# FMC_prototype.net
KiCad netlist of a schematic drawn in EAGLE
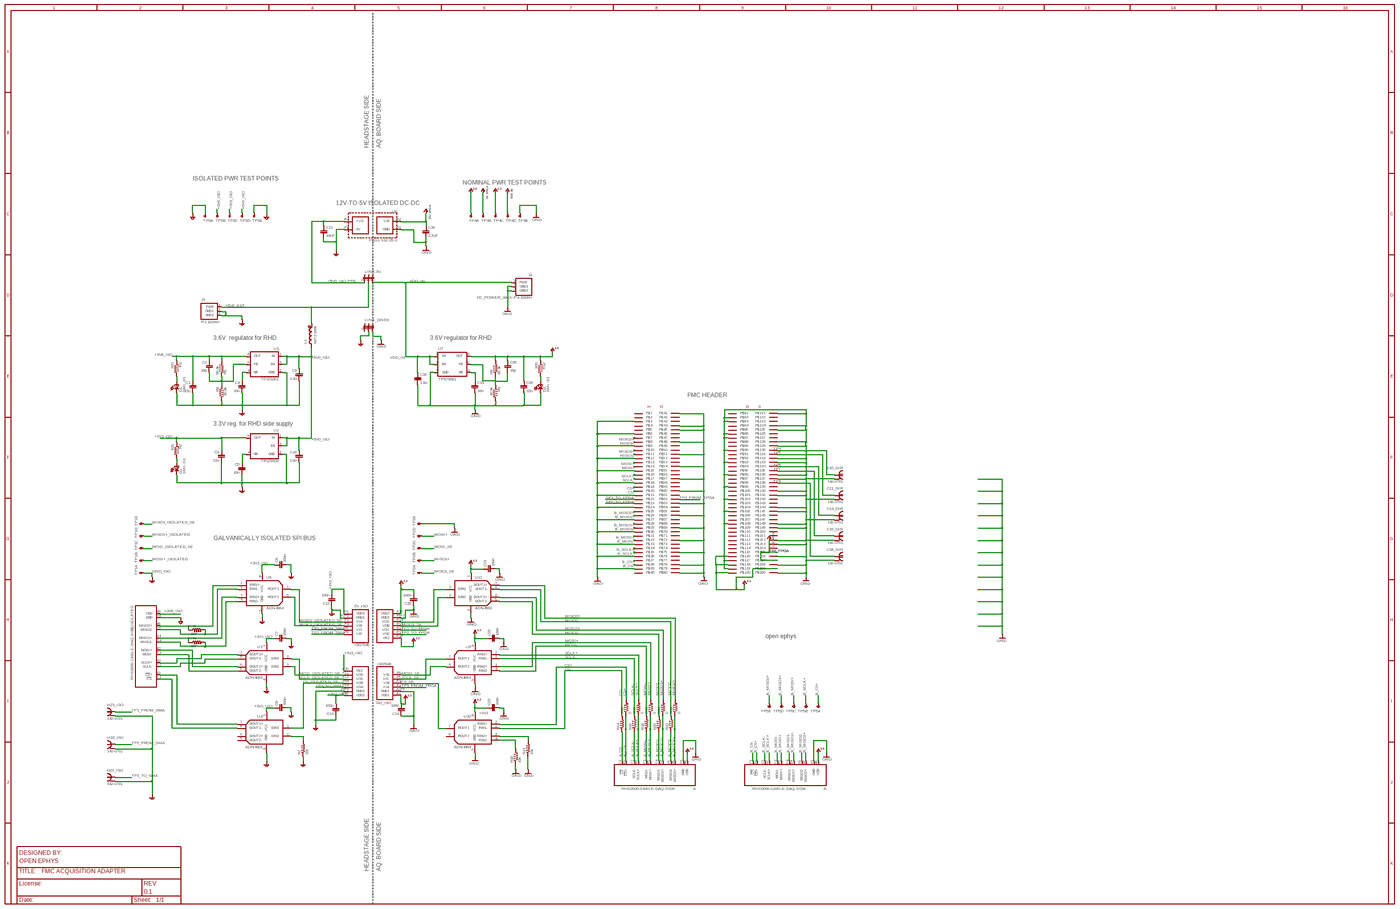
[diagram p0: schematic, sheet 1, overview]
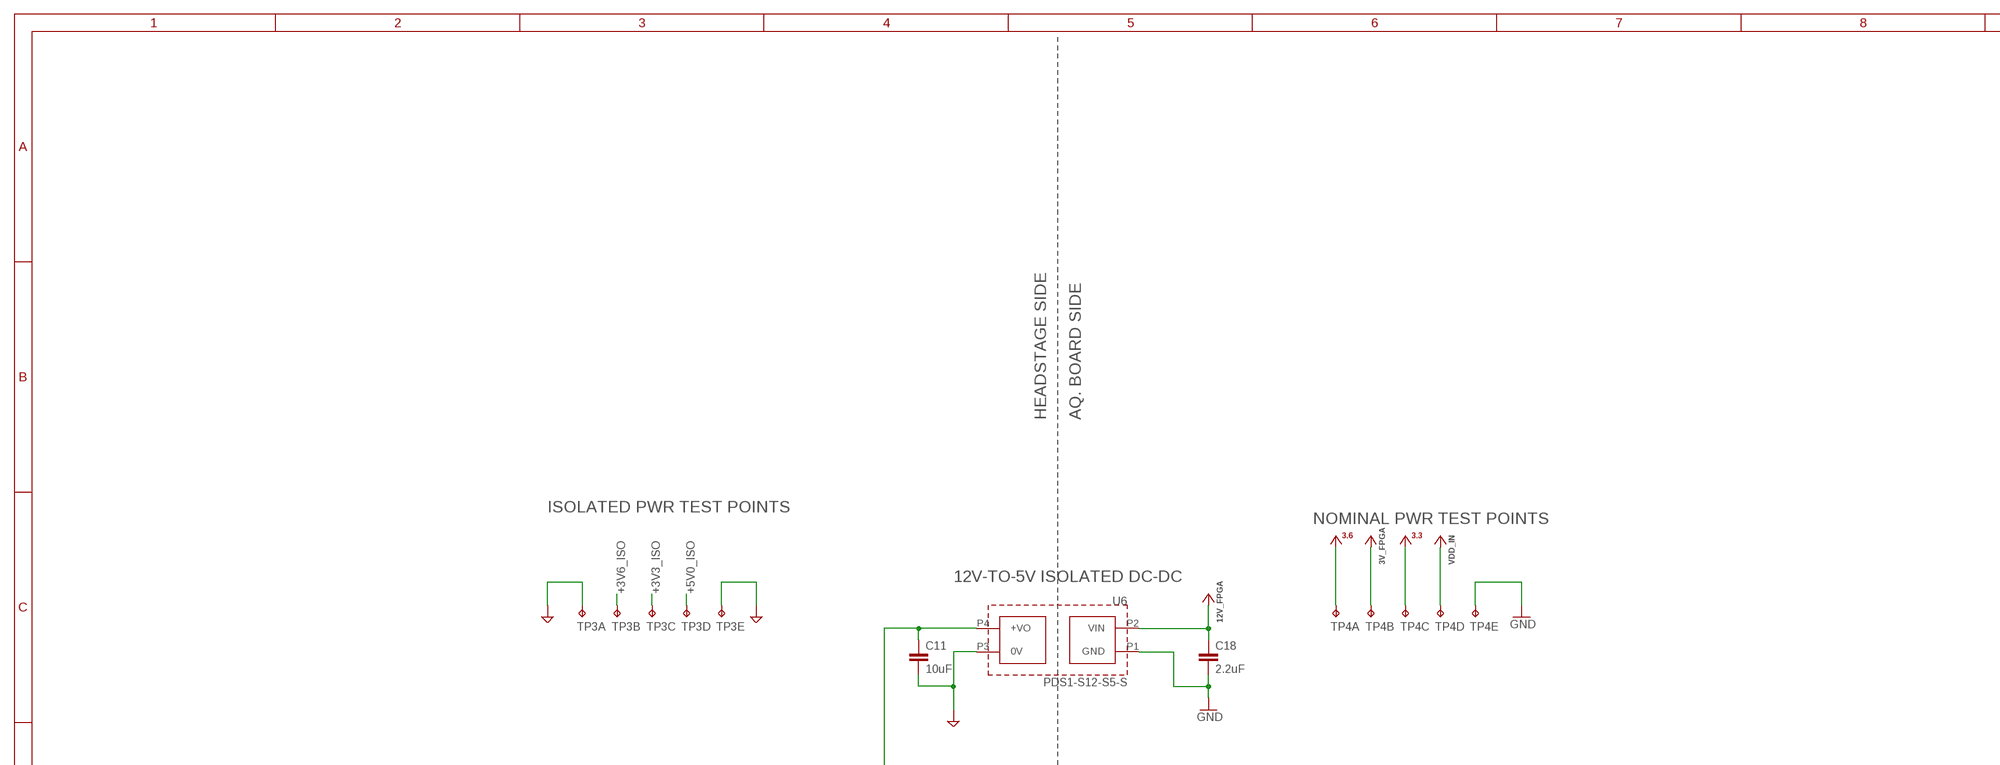
[diagram p1: schematic, sheet 1, part 1 of 4]
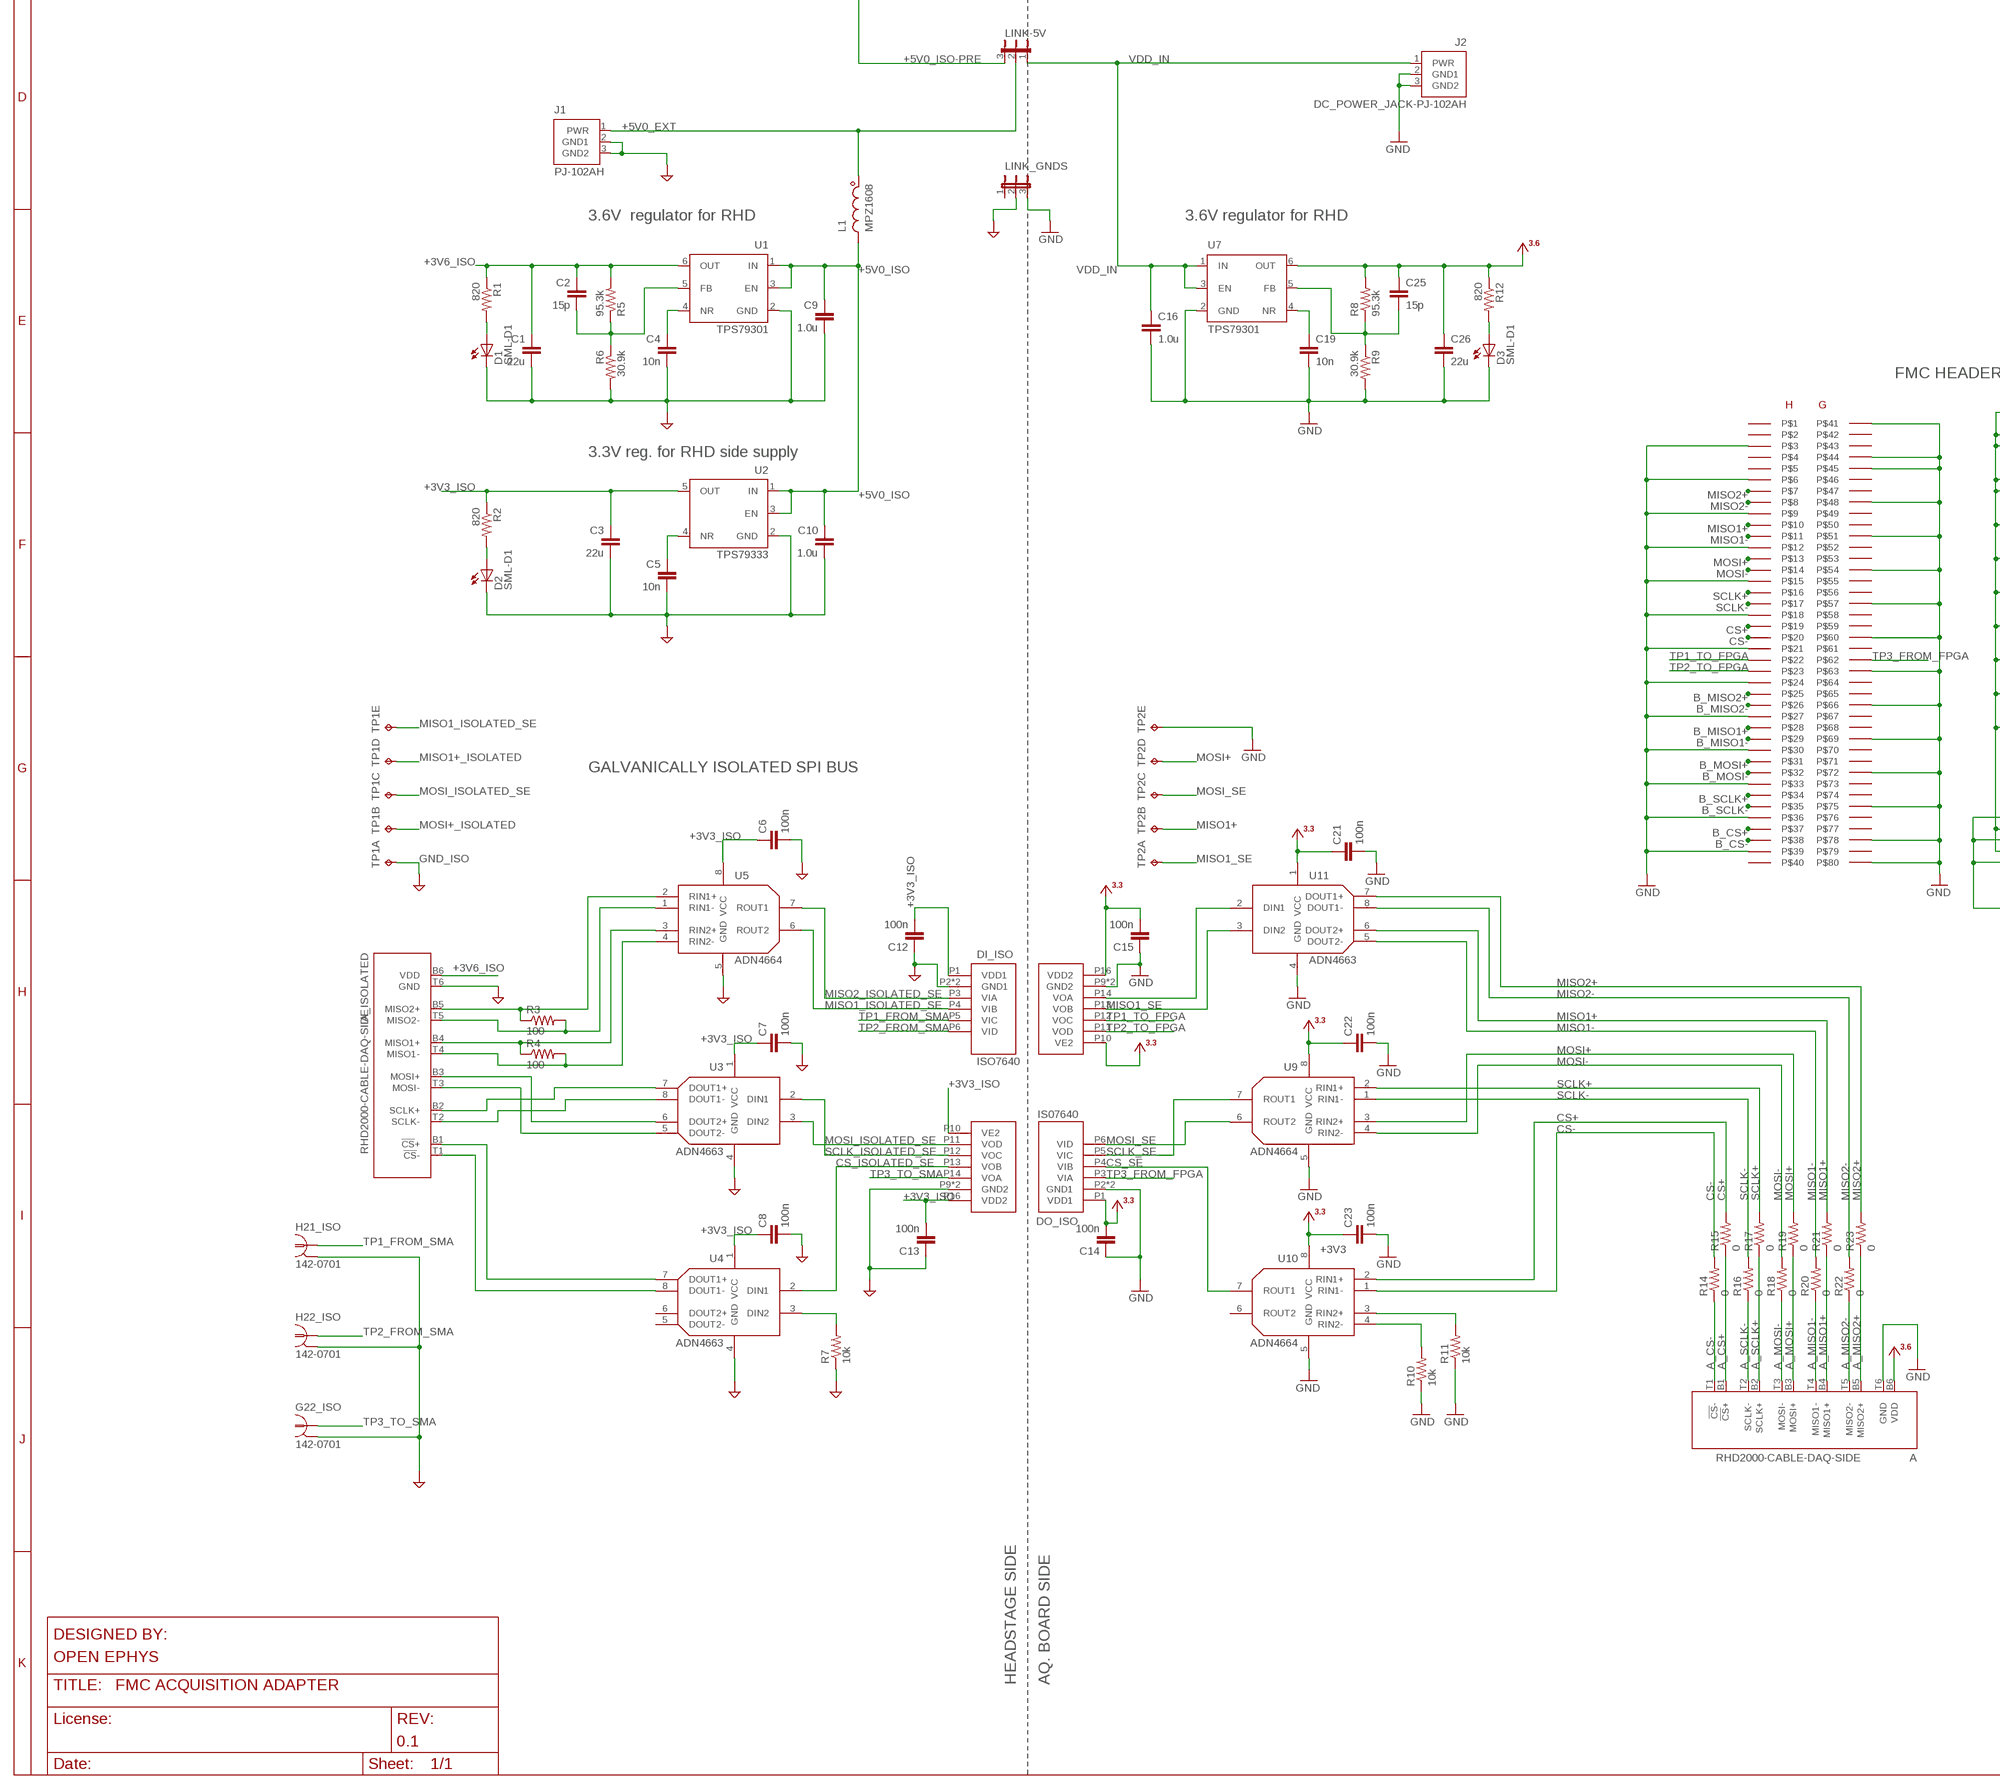
[diagram p2: schematic, sheet 1, part 2 of 4]
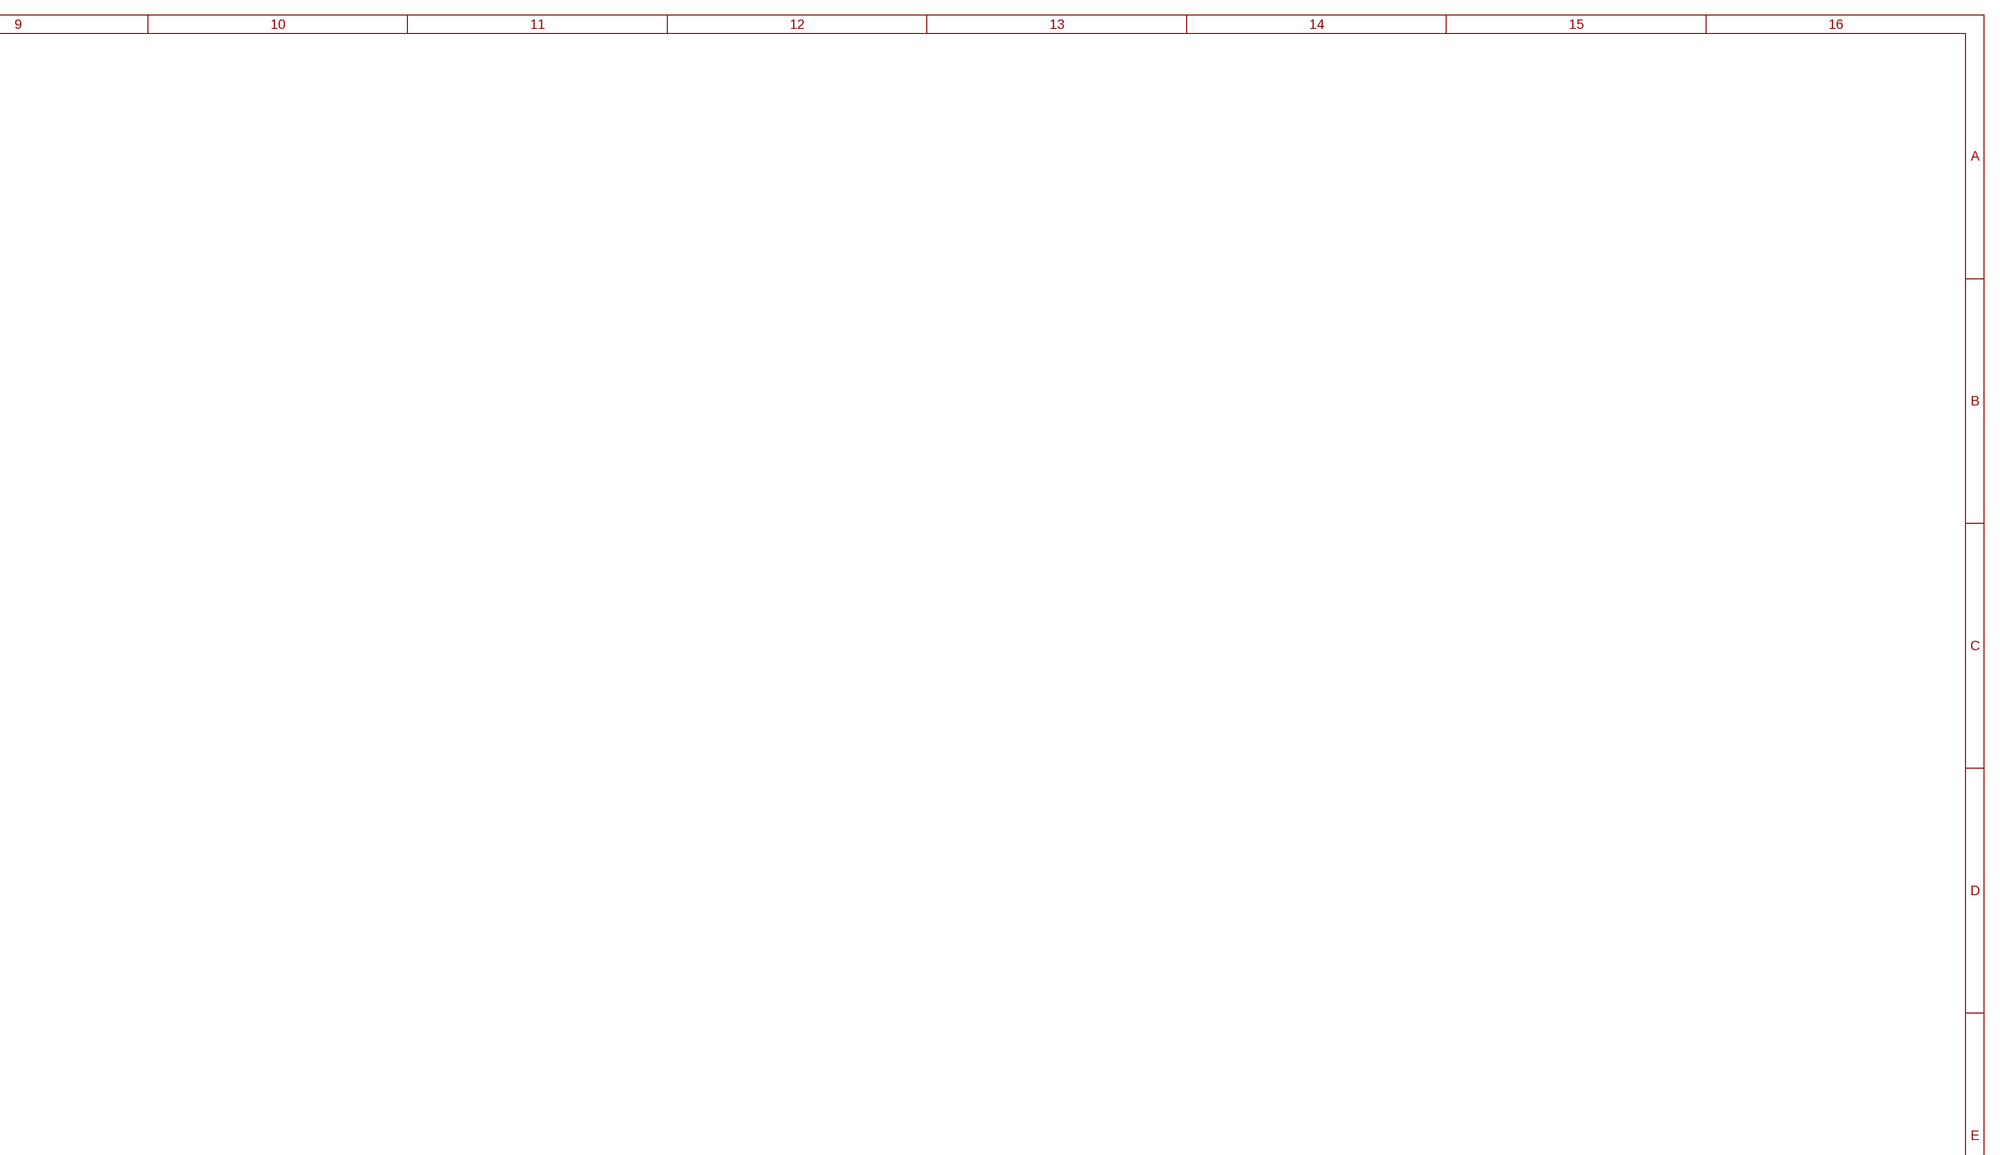
[diagram p3: schematic, sheet 1, part 3 of 4]
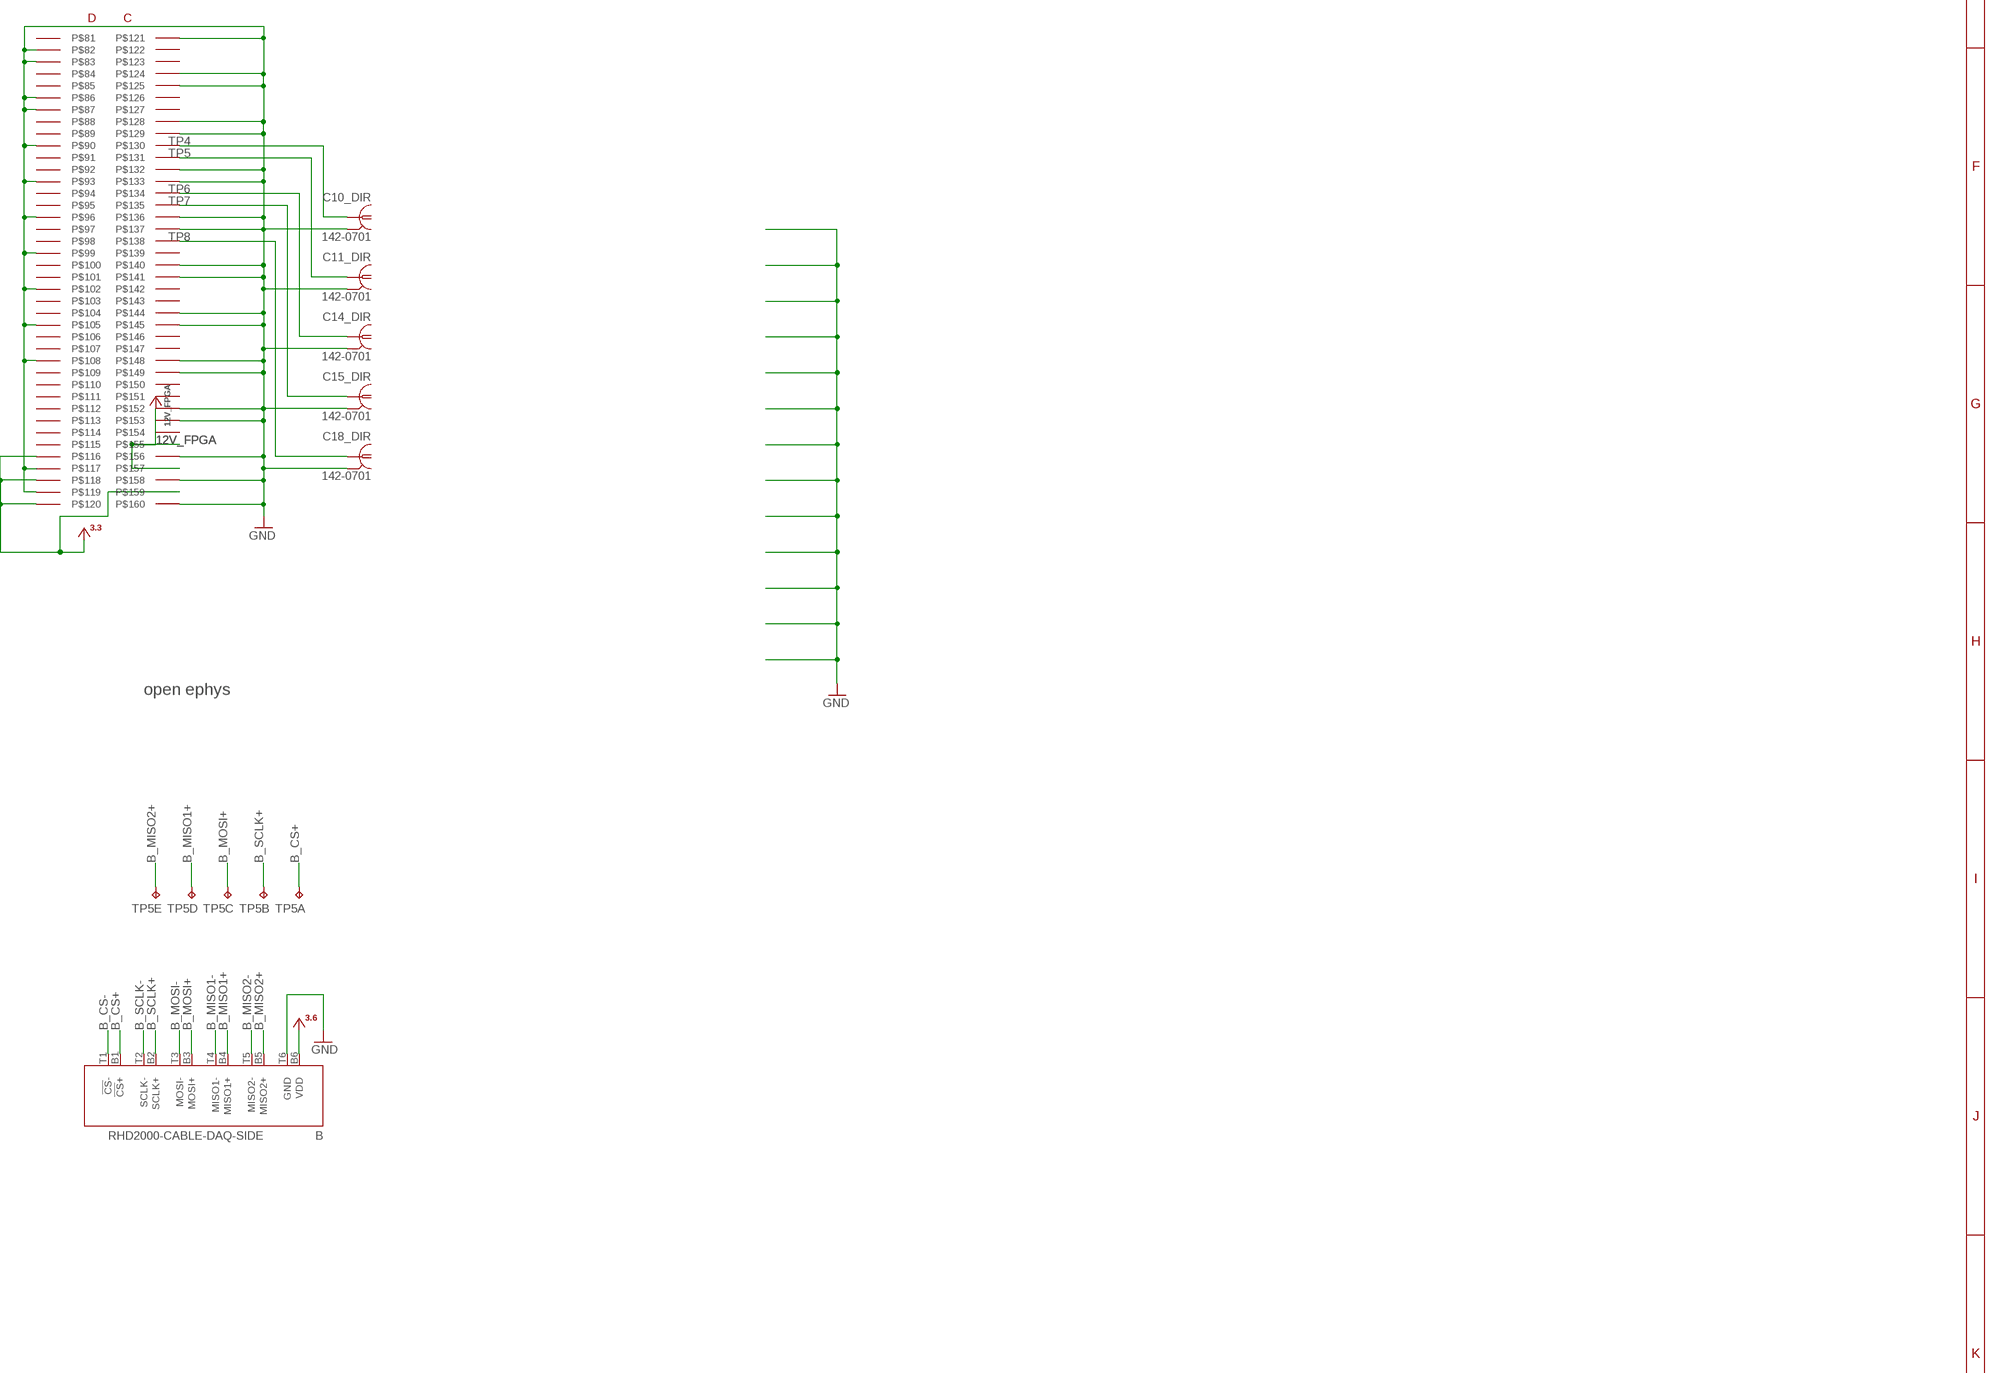
[diagram p4: schematic, sheet 1, part 4 of 4]

(export (version "E")
  (design (tool "Eeschema 10.0.6"))
  (components
    (comp (ref "A")
      (value "RHD2000-CABLE-DAQ-SIDE")
      (footprint "eagle-import:OMNETICS_PZN-12-AA")
      (libsource (lib "eagle-import") (part "RHD2000-CABLE-DAQ-SIDE"))
    )
    (comp (ref "A_ISOLATED")
      (value "RHD2000-CABLE-DAQ-SIDE")
      (footprint "eagle-import:OMNETICS_PZN-12-AA")
      (libsource (lib "eagle-import") (part "RHD2000-CABLE-DAQ-SIDE"))
    )
    (comp (ref "B")
      (value "RHD2000-CABLE-DAQ-SIDE")
      (footprint "eagle-import:OMNETICS_PZN-12-AA")
      (libsource (lib "eagle-import") (part "RHD2000-CABLE-DAQ-SIDE"))
    )
    (comp (ref "C1")
      (value "22u")
      (footprint "eagle-import:1206")
      (libsource (lib "eagle-import") (part "C_1206"))
    )
    (comp (ref "C2")
      (value "15p")
      (footprint "eagle-import:0603")
      (libsource (lib "eagle-import") (part "C_0603"))
    )
    (comp (ref "C3")
      (value "22u")
      (footprint "eagle-import:1206")
      (libsource (lib "eagle-import") (part "C_1206"))
    )
    (comp (ref "C4")
      (value "10n")
      (footprint "eagle-import:0603")
      (libsource (lib "eagle-import") (part "C_0603"))
    )
    (comp (ref "C5")
      (value "10n")
      (footprint "eagle-import:0603")
      (libsource (lib "eagle-import") (part "C_0603"))
    )
    (comp (ref "C6")
      (value "100n")
      (footprint "eagle-import:0603")
      (libsource (lib "eagle-import") (part "C_0603"))
    )
    (comp (ref "C7")
      (value "100n")
      (footprint "eagle-import:0603")
      (libsource (lib "eagle-import") (part "C_0603"))
    )
    (comp (ref "C8")
      (value "100n")
      (footprint "eagle-import:0603")
      (libsource (lib "eagle-import") (part "C_0603"))
    )
    (comp (ref "C9")
      (value "1.0u")
      (footprint "eagle-import:0805")
      (libsource (lib "eagle-import") (part "C_0805"))
    )
    (comp (ref "C10")
      (value "1.0u")
      (footprint "eagle-import:0805")
      (libsource (lib "eagle-import") (part "C_0805"))
    )
    (comp (ref "C10_DIR")
      (value "142-0701")
      (footprint "eagle-import:SMA_JACK_142-0701-201")
      (libsource (lib "eagle-import") (part "COAX_SMA-VERT"))
    )
    (comp (ref "C11")
      (value "10uF")
      (footprint "eagle-import:1206")
      (libsource (lib "eagle-import") (part "jonnew_C_1206"))
    )
    (comp (ref "C11_DIR")
      (value "142-0701")
      (footprint "eagle-import:SMA_JACK_142-0701-201")
      (libsource (lib "eagle-import") (part "COAX_SMA-VERT"))
    )
    (comp (ref "C12")
      (value "100n")
      (footprint "eagle-import:0603")
      (libsource (lib "eagle-import") (part "C_0603"))
    )
    (comp (ref "C13")
      (value "100n")
      (footprint "eagle-import:0603")
      (libsource (lib "eagle-import") (part "C_0603"))
    )
    (comp (ref "C14")
      (value "100n")
      (footprint "eagle-import:0603")
      (libsource (lib "eagle-import") (part "C_0603"))
    )
    (comp (ref "C14_DIR")
      (value "142-0701")
      (footprint "eagle-import:SMA_JACK_142-0701-201")
      (libsource (lib "eagle-import") (part "COAX_SMA-VERT"))
    )
    (comp (ref "C15")
      (value "100n")
      (footprint "eagle-import:0603")
      (libsource (lib "eagle-import") (part "C_0603"))
    )
    (comp (ref "C15_DIR")
      (value "142-0701")
      (footprint "eagle-import:SMA_JACK_142-0701-201")
      (libsource (lib "eagle-import") (part "COAX_SMA-VERT"))
    )
    (comp (ref "C16")
      (value "1.0u")
      (footprint "eagle-import:0805")
      (libsource (lib "eagle-import") (part "C_0805"))
    )
    (comp (ref "C18")
      (value "2.2uF")
      (footprint "eagle-import:1206")
      (libsource (lib "eagle-import") (part "jonnew_C_1206"))
    )
    (comp (ref "C18_DIR")
      (value "142-0701")
      (footprint "eagle-import:SMA_JACK_142-0701-201")
      (libsource (lib "eagle-import") (part "COAX_SMA-VERT"))
    )
    (comp (ref "C19")
      (value "10n")
      (footprint "eagle-import:0603")
      (libsource (lib "eagle-import") (part "C_0603"))
    )
    (comp (ref "C21")
      (value "100n")
      (footprint "eagle-import:0603")
      (libsource (lib "eagle-import") (part "C_0603"))
    )
    (comp (ref "C22")
      (value "100n")
      (footprint "eagle-import:0603")
      (libsource (lib "eagle-import") (part "C_0603"))
    )
    (comp (ref "C23")
      (value "100n")
      (footprint "eagle-import:0603")
      (libsource (lib "eagle-import") (part "C_0603"))
    )
    (comp (ref "C25")
      (value "15p")
      (footprint "eagle-import:0603")
      (libsource (lib "eagle-import") (part "C_0603"))
    )
    (comp (ref "C26")
      (value "22u")
      (footprint "eagle-import:1206")
      (libsource (lib "eagle-import") (part "C_1206"))
    )
    (comp (ref "D1")
      (value "SML-D1")
      (footprint "eagle-import:LED-0603")
      (libsource (lib "eagle-import") (part "LED_0603"))
    )
    (comp (ref "D2")
      (value "SML-D1")
      (footprint "eagle-import:LED-0603")
      (libsource (lib "eagle-import") (part "LED_0603"))
    )
    (comp (ref "D3")
      (value "SML-D1")
      (footprint "eagle-import:LED-0603")
      (libsource (lib "eagle-import") (part "LED_0603"))
    )
    (comp (ref "DI_ISO")
      (value "ISO7640")
      (footprint "eagle-import:SOIC_WIDE_16")
      (libsource (lib "eagle-import") (part "ADUM3440"))
    )
    (comp (ref "DO_ISO")
      (value "IS07640")
      (footprint "eagle-import:SOIC_WIDE_16")
      (libsource (lib "eagle-import") (part "ADUM3440"))
    )
    (comp (ref "FMC")
      (value "FMC_LPC_160_PIN")
      (footprint "eagle-import:FMC_LPC_MALE_WITH_SP601_BSILK")
      (libsource (lib "eagle-import") (part "FMC_LPC_160_PIN"))
    )
    (comp (ref "G22_ISO")
      (value "142-0701")
      (footprint "eagle-import:SMA_JACK_142-0701-201")
      (libsource (lib "eagle-import") (part "COAX_SMA-VERT"))
    )
    (comp (ref "H21_ISO")
      (value "142-0701")
      (footprint "eagle-import:SMA_JACK_142-0701-201")
      (libsource (lib "eagle-import") (part "COAX_SMA-VERT"))
    )
    (comp (ref "H22_ISO")
      (value "142-0701")
      (footprint "eagle-import:SMA_JACK_142-0701-201")
      (libsource (lib "eagle-import") (part "COAX_SMA-VERT"))
    )
    (comp (ref "J1")
      (value "PJ-102AH")
      (footprint "eagle-import:PJ-102AH")
      (libsource (lib "eagle-import") (part "DC_POWER_JACK-PJ-102AH"))
    )
    (comp (ref "J2")
      (value "DC_POWER_JACK-PJ-102AH")
      (footprint "eagle-import:PJ-102AH")
      (libsource (lib "eagle-import") (part "DC_POWER_JACK-PJ-102AH"))
    )
    (comp (ref "L1")
      (value "MPZ1608")
      (footprint "eagle-import:0603")
      (libsource (lib "eagle-import") (part "L_0603"))
    )
    (comp (ref "LINK-5V")
      (value "JP2E")
      (footprint "eagle-import:JP2")
      (libsource (lib "eagle-import") (part "JP2E"))
    )
    (comp (ref "LINK_GNDS")
      (value "JP2E")
      (footprint "eagle-import:JP2")
      (libsource (lib "eagle-import") (part "JP2E"))
    )
    (comp (ref "R1")
      (value "820")
      (footprint "eagle-import:0603")
      (libsource (lib "eagle-import") (part "R_0603"))
    )
    (comp (ref "R2")
      (value "820")
      (footprint "eagle-import:0603")
      (libsource (lib "eagle-import") (part "R_0603"))
    )
    (comp (ref "R3")
      (value "100")
      (footprint "eagle-import:0603")
      (libsource (lib "eagle-import") (part "R_0603"))
    )
    (comp (ref "R4")
      (value "100")
      (footprint "eagle-import:0603")
      (libsource (lib "eagle-import") (part "R_0603"))
    )
    (comp (ref "R5")
      (value "95.3k")
      (footprint "eagle-import:0603")
      (libsource (lib "eagle-import") (part "R_0603"))
    )
    (comp (ref "R6")
      (value "30.9k")
      (footprint "eagle-import:0603")
      (libsource (lib "eagle-import") (part "R_0603"))
    )
    (comp (ref "R7")
      (value "10k")
      (footprint "eagle-import:0603")
      (libsource (lib "eagle-import") (part "R_0603"))
    )
    (comp (ref "R8")
      (value "95.3k")
      (footprint "eagle-import:0603")
      (libsource (lib "eagle-import") (part "R_0603"))
    )
    (comp (ref "R9")
      (value "30.9k")
      (footprint "eagle-import:0603")
      (libsource (lib "eagle-import") (part "R_0603"))
    )
    (comp (ref "R10")
      (value "10k")
      (footprint "eagle-import:0603")
      (libsource (lib "eagle-import") (part "R_0603"))
    )
    (comp (ref "R11")
      (value "10k")
      (footprint "eagle-import:0603")
      (libsource (lib "eagle-import") (part "R_0603"))
    )
    (comp (ref "R12")
      (value "820")
      (footprint "eagle-import:0603")
      (libsource (lib "eagle-import") (part "R_0603"))
    )
    (comp (ref "R14")
      (value "0")
      (footprint "eagle-import:0603")
      (libsource (lib "eagle-import") (part "R_0603"))
    )
    (comp (ref "R15")
      (value "0")
      (footprint "eagle-import:0603")
      (libsource (lib "eagle-import") (part "R_0603"))
    )
    (comp (ref "R16")
      (value "0")
      (footprint "eagle-import:0603")
      (libsource (lib "eagle-import") (part "R_0603"))
    )
    (comp (ref "R17")
      (value "0")
      (footprint "eagle-import:0603")
      (libsource (lib "eagle-import") (part "R_0603"))
    )
    (comp (ref "R18")
      (value "0")
      (footprint "eagle-import:0603")
      (libsource (lib "eagle-import") (part "R_0603"))
    )
    (comp (ref "R19")
      (value "0")
      (footprint "eagle-import:0603")
      (libsource (lib "eagle-import") (part "R_0603"))
    )
    (comp (ref "R20")
      (value "0")
      (footprint "eagle-import:0603")
      (libsource (lib "eagle-import") (part "R_0603"))
    )
    (comp (ref "R21")
      (value "0")
      (footprint "eagle-import:0603")
      (libsource (lib "eagle-import") (part "R_0603"))
    )
    (comp (ref "R22")
      (value "0")
      (footprint "eagle-import:0603")
      (libsource (lib "eagle-import") (part "R_0603"))
    )
    (comp (ref "R23")
      (value "0")
      (footprint "eagle-import:0603")
      (libsource (lib "eagle-import") (part "R_0603"))
    )
    (comp (ref "TP1")
      (value "TP5P5-25-13")
      (footprint "eagle-import:P5-25-13")
      (libsource (lib "eagle-import") (part "TP5P5-25-13"))
    )
    (comp (ref "TP2")
      (value "TP5P5-25-13")
      (footprint "eagle-import:P5-25-13")
      (libsource (lib "eagle-import") (part "TP5P5-25-13"))
    )
    (comp (ref "TP3")
      (value "TP5P5-25-13")
      (footprint "eagle-import:P5-25-13")
      (libsource (lib "eagle-import") (part "TP5P5-25-13"))
    )
    (comp (ref "TP4")
      (value "TP5P5-25-13")
      (footprint "eagle-import:P5-25-13")
      (libsource (lib "eagle-import") (part "TP5P5-25-13"))
    )
    (comp (ref "TP5")
      (value "TP5P5-25-13")
      (footprint "eagle-import:P5-25-13")
      (libsource (lib "eagle-import") (part "TP5P5-25-13"))
    )
    (comp (ref "U$1")
      (value "OPEN_EPHYS_LOGO")
      (footprint "eagle-import:OPEN_EPHYS_LOGO")
      (libsource (lib "eagle-import") (part "OPEN_EPHYS_LOGO"))
    )
    (comp (ref "U1")
      (value "TPS79301")
      (footprint "eagle-import:SOT-23-6")
      (libsource (lib "eagle-import") (part "TPS79301"))
    )
    (comp (ref "U2")
      (value "TPS79333")
      (footprint "eagle-import:SOT-23-5")
      (libsource (lib "eagle-import") (part "TPS79333"))
    )
    (comp (ref "U3")
      (value "ADN4663")
      (footprint "eagle-import:SOIC127P500X400-8N")
      (libsource (lib "eagle-import") (part "ADN4663_SOIC"))
    )
    (comp (ref "U4")
      (value "ADN4663")
      (footprint "eagle-import:SOIC127P500X400-8N")
      (libsource (lib "eagle-import") (part "ADN4663_SOIC"))
    )
    (comp (ref "U5")
      (value "ADN4664")
      (footprint "eagle-import:SOIC127P500X400-8N")
      (libsource (lib "eagle-import") (part "ADN4664_SOIC"))
    )
    (comp (ref "U6")
      (value "PDS1-S12-S5-S")
      (footprint "eagle-import:PDS1")
      (libsource (lib "eagle-import") (part "PDS1"))
    )
    (comp (ref "U7")
      (value "TPS79301")
      (footprint "eagle-import:SOT-23-6")
      (libsource (lib "eagle-import") (part "TPS79301"))
    )
    (comp (ref "U9")
      (value "ADN4664")
      (footprint "eagle-import:SOIC127P500X400-8N")
      (libsource (lib "eagle-import") (part "ADN4664_SOIC"))
    )
    (comp (ref "U10")
      (value "ADN4664")
      (footprint "eagle-import:SOIC127P500X400-8N")
      (libsource (lib "eagle-import") (part "ADN4664_SOIC"))
    )
    (comp (ref "U11")
      (value "ADN4663")
      (footprint "eagle-import:SOIC127P500X400-8N")
      (libsource (lib "eagle-import") (part "ADN4663_SOIC"))
    )
  )
  (nets
    (net (code "1") (name "+3V3") (class "Default")
      (node (ref "C14") (pin "2") (pinfunction "2_2") (pintype "passive"))
      (node (ref "C15") (pin "2") (pinfunction "2_2") (pintype "passive"))
      (node (ref "C21") (pin "1") (pinfunction "1_1") (pintype "passive"))
      (node (ref "C22") (pin "1") (pinfunction "1_1") (pintype "passive"))
      (node (ref "C23") (pin "1") (pinfunction "1_1") (pintype "passive"))
      (node (ref "DI_ISO") (pin "P10") (pinfunction "VE2_P10") (pintype "bidirectional"))
      (node (ref "DI_ISO") (pin "P16") (pinfunction "VDD2_P16") (pintype "bidirectional"))
      (node (ref "DO_ISO") (pin "P1") (pinfunction "VDD1_P1") (pintype "bidirectional"))
      (node (ref "FMC") (pin "P$116") (pinfunction "P$116_P$116") (pintype "bidirectional"))
      (node (ref "FMC") (pin "P$118") (pinfunction "P$118_P$118") (pintype "bidirectional"))
      (node (ref "FMC") (pin "P$120") (pinfunction "P$120_P$120") (pintype "bidirectional"))
      (node (ref "FMC") (pin "P$159") (pinfunction "P$159_P$159") (pintype "bidirectional"))
      (node (ref "TP4") (pin "TP-2") (pinfunction "TP_TP-2") (pintype "input"))
      (node (ref "TP4") (pin "TP-3") (pinfunction "TP_TP-3") (pintype "input"))
      (node (ref "U10") (pin "8") (pinfunction "VCC_8") (pintype "bidirectional"))
      (node (ref "U11") (pin "1") (pinfunction "VCC_1") (pintype "bidirectional"))
      (node (ref "U9") (pin "8") (pinfunction "VCC_8") (pintype "bidirectional"))
    )
    (net (code "2") (name "+3V6") (class "Default")
      (node (ref "A") (pin "B6") (pinfunction "VDD_B6") (pintype "bidirectional"))
      (node (ref "B") (pin "B6") (pinfunction "VDD_B6") (pintype "bidirectional"))
      (node (ref "C25") (pin "1") (pinfunction "1_1") (pintype "passive"))
      (node (ref "C26") (pin "1") (pinfunction "1_1") (pintype "passive"))
      (node (ref "R12") (pin "1") (pinfunction "1_1") (pintype "passive"))
      (node (ref "R8") (pin "2") (pinfunction "2_2") (pintype "passive"))
      (node (ref "TP4") (pin "TP-1") (pinfunction "TP_TP-1") (pintype "input"))
      (node (ref "U7") (pin "6") (pinfunction "OUT_6") (pintype "power_in"))
    )
    (net (code "3") (name "/+3V3_ISO") (class "Default")
      (node (ref "C12") (pin "2") (pinfunction "2_2") (pintype "passive"))
      (node (ref "C13") (pin "2") (pinfunction "2_2") (pintype "passive"))
      (node (ref "C3") (pin "1") (pinfunction "1_1") (pintype "passive"))
      (node (ref "C6") (pin "1") (pinfunction "1_1") (pintype "passive"))
      (node (ref "C7") (pin "1") (pinfunction "1_1") (pintype "passive"))
      (node (ref "C8") (pin "1") (pinfunction "1_1") (pintype "passive"))
      (node (ref "DI_ISO") (pin "P1") (pinfunction "VDD1_P1") (pintype "bidirectional"))
      (node (ref "DO_ISO") (pin "P10") (pinfunction "VE2_P10") (pintype "bidirectional"))
      (node (ref "DO_ISO") (pin "P16") (pinfunction "VDD2_P16") (pintype "bidirectional"))
      (node (ref "R2") (pin "1") (pinfunction "1_1") (pintype "passive"))
      (node (ref "TP3") (pin "TP-3") (pinfunction "TP_TP-3") (pintype "input"))
      (node (ref "U2") (pin "5") (pinfunction "OUT_5") (pintype "power_in"))
      (node (ref "U3") (pin "1") (pinfunction "VCC_1") (pintype "bidirectional"))
      (node (ref "U4") (pin "1") (pinfunction "VCC_1") (pintype "bidirectional"))
      (node (ref "U5") (pin "8") (pinfunction "VCC_8") (pintype "bidirectional"))
    )
    (net (code "4") (name "/+3V6_ISO") (class "Default")
      (node (ref "A_ISOLATED") (pin "B6") (pinfunction "VDD_B6") (pintype "bidirectional"))
      (node (ref "C1") (pin "1") (pinfunction "1_1") (pintype "passive"))
      (node (ref "C2") (pin "1") (pinfunction "1_1") (pintype "passive"))
      (node (ref "R1") (pin "1") (pinfunction "1_1") (pintype "passive"))
      (node (ref "R5") (pin "2") (pinfunction "2_2") (pintype "passive"))
      (node (ref "TP3") (pin "TP-2") (pinfunction "TP_TP-2") (pintype "input"))
      (node (ref "U1") (pin "6") (pinfunction "OUT_6") (pintype "power_in"))
    )
    (net (code "5") (name "/+5V0_EXT") (class "Default")
      (node (ref "J1") (pin "1") (pinfunction "PWR_1") (pintype "power_in"))
      (node (ref "L1") (pin "1") (pinfunction "1_1") (pintype "passive"))
      (node (ref "LINK-5V") (pin "2") (pinfunction "2_2") (pintype "passive"))
    )
    (net (code "6") (name "/+5V0_ISO") (class "Default")
      (node (ref "C10") (pin "1") (pinfunction "1_1") (pintype "passive"))
      (node (ref "C9") (pin "1") (pinfunction "1_1") (pintype "passive"))
      (node (ref "L1") (pin "2") (pinfunction "2_2") (pintype "passive"))
      (node (ref "TP3") (pin "TP-4") (pinfunction "TP_TP-4") (pintype "input"))
      (node (ref "U1") (pin "1") (pinfunction "IN_1") (pintype "power_in"))
      (node (ref "U1") (pin "3") (pinfunction "EN_3") (pintype "input"))
      (node (ref "U2") (pin "1") (pinfunction "IN_1") (pintype "power_in"))
      (node (ref "U2") (pin "3") (pinfunction "EN_3") (pintype "input"))
    )
    (net (code "7") (name "/+5V0_ISO-PRE") (class "Default")
      (node (ref "C11") (pin "1") (pinfunction "1_1") (pintype "passive"))
      (node (ref "LINK-5V") (pin "3") (pinfunction "3_3") (pintype "passive"))
      (node (ref "U6") (pin "P4") (pinfunction "+VO_P4") (pintype "bidirectional"))
    )
    (net (code "8") (name "/12V_FPGA") (class "Default")
      (node (ref "C18") (pin "1") (pinfunction "1_1") (pintype "passive"))
      (node (ref "FMC") (pin "P$155") (pinfunction "P$155_P$155") (pintype "bidirectional"))
      (node (ref "FMC") (pin "P$157") (pinfunction "P$157_P$157") (pintype "bidirectional"))
      (node (ref "U6") (pin "P2") (pinfunction "VIN_P2") (pintype "bidirectional"))
    )
    (net (code "9") (name "/A_CS+") (class "Default")
      (node (ref "A") (pin "B1") (pinfunction "~{CS}+_B1") (pintype "bidirectional"))
      (node (ref "R15") (pin "1") (pinfunction "1_1") (pintype "passive"))
    )
    (net (code "10") (name "/A_CS-") (class "Default")
      (node (ref "A") (pin "T1") (pinfunction "~{CS}-_T1") (pintype "bidirectional"))
      (node (ref "R14") (pin "1") (pinfunction "1_1") (pintype "passive"))
    )
    (net (code "11") (name "/A_MISO1+") (class "Default")
      (node (ref "A") (pin "B4") (pinfunction "MISO1+_B4") (pintype "bidirectional"))
      (node (ref "R21") (pin "1") (pinfunction "1_1") (pintype "passive"))
    )
    (net (code "12") (name "/A_MISO1-") (class "Default")
      (node (ref "A") (pin "T4") (pinfunction "MISO1-_T4") (pintype "bidirectional"))
      (node (ref "R20") (pin "1") (pinfunction "1_1") (pintype "passive"))
    )
    (net (code "13") (name "/A_MISO2+") (class "Default")
      (node (ref "A") (pin "B5") (pinfunction "MISO2+_B5") (pintype "bidirectional"))
      (node (ref "R23") (pin "1") (pinfunction "1_1") (pintype "passive"))
    )
    (net (code "14") (name "/A_MISO2-") (class "Default")
      (node (ref "A") (pin "T5") (pinfunction "MISO2-_T5") (pintype "bidirectional"))
      (node (ref "R22") (pin "1") (pinfunction "1_1") (pintype "passive"))
    )
    (net (code "15") (name "/A_MOSI+") (class "Default")
      (node (ref "A") (pin "B3") (pinfunction "MOSI+_B3") (pintype "bidirectional"))
      (node (ref "R19") (pin "1") (pinfunction "1_1") (pintype "passive"))
    )
    (net (code "16") (name "/A_MOSI-") (class "Default")
      (node (ref "A") (pin "T3") (pinfunction "MOSI-_T3") (pintype "bidirectional"))
      (node (ref "R18") (pin "1") (pinfunction "1_1") (pintype "passive"))
    )
    (net (code "17") (name "/A_SCLK+") (class "Default")
      (node (ref "A") (pin "B2") (pinfunction "SCLK+_B2") (pintype "bidirectional"))
      (node (ref "R17") (pin "1") (pinfunction "1_1") (pintype "passive"))
    )
    (net (code "18") (name "/A_SCLK-") (class "Default")
      (node (ref "A") (pin "T2") (pinfunction "SCLK-_T2") (pintype "bidirectional"))
      (node (ref "R16") (pin "1") (pinfunction "1_1") (pintype "passive"))
    )
    (net (code "19") (name "/B_CS+") (class "Default")
      (node (ref "B") (pin "B1") (pinfunction "~{CS}+_B1") (pintype "bidirectional"))
      (node (ref "FMC") (pin "P$37") (pinfunction "P$37_P$37") (pintype "bidirectional"))
      (node (ref "TP5") (pin "TP-1") (pinfunction "TP_TP-1") (pintype "input"))
    )
    (net (code "20") (name "/B_CS-") (class "Default")
      (node (ref "B") (pin "T1") (pinfunction "~{CS}-_T1") (pintype "bidirectional"))
      (node (ref "FMC") (pin "P$38") (pinfunction "P$38_P$38") (pintype "bidirectional"))
    )
    (net (code "21") (name "/B_MISO1+") (class "Default")
      (node (ref "B") (pin "B4") (pinfunction "MISO1+_B4") (pintype "bidirectional"))
      (node (ref "FMC") (pin "P$28") (pinfunction "P$28_P$28") (pintype "bidirectional"))
      (node (ref "TP5") (pin "TP-4") (pinfunction "TP_TP-4") (pintype "input"))
    )
    (net (code "22") (name "/B_MISO1-") (class "Default")
      (node (ref "B") (pin "T4") (pinfunction "MISO1-_T4") (pintype "bidirectional"))
      (node (ref "FMC") (pin "P$29") (pinfunction "P$29_P$29") (pintype "bidirectional"))
    )
    (net (code "23") (name "/B_MISO2+") (class "Default")
      (node (ref "B") (pin "B5") (pinfunction "MISO2+_B5") (pintype "bidirectional"))
      (node (ref "FMC") (pin "P$25") (pinfunction "P$25_P$25") (pintype "bidirectional"))
      (node (ref "TP5") (pin "TP-5") (pinfunction "TP_TP-5") (pintype "input"))
    )
    (net (code "24") (name "/B_MISO2-") (class "Default")
      (node (ref "B") (pin "T5") (pinfunction "MISO2-_T5") (pintype "bidirectional"))
      (node (ref "FMC") (pin "P$26") (pinfunction "P$26_P$26") (pintype "bidirectional"))
    )
    (net (code "25") (name "/B_MOSI+") (class "Default")
      (node (ref "B") (pin "B3") (pinfunction "MOSI+_B3") (pintype "bidirectional"))
      (node (ref "FMC") (pin "P$31") (pinfunction "P$31_P$31") (pintype "bidirectional"))
      (node (ref "TP5") (pin "TP-3") (pinfunction "TP_TP-3") (pintype "input"))
    )
    (net (code "26") (name "/B_MOSI-") (class "Default")
      (node (ref "B") (pin "T3") (pinfunction "MOSI-_T3") (pintype "bidirectional"))
      (node (ref "FMC") (pin "P$32") (pinfunction "P$32_P$32") (pintype "bidirectional"))
    )
    (net (code "27") (name "/B_SCLK+") (class "Default")
      (node (ref "B") (pin "B2") (pinfunction "SCLK+_B2") (pintype "bidirectional"))
      (node (ref "FMC") (pin "P$34") (pinfunction "P$34_P$34") (pintype "bidirectional"))
      (node (ref "TP5") (pin "TP-2") (pinfunction "TP_TP-2") (pintype "input"))
    )
    (net (code "28") (name "/B_SCLK-") (class "Default")
      (node (ref "B") (pin "T2") (pinfunction "SCLK-_T2") (pintype "bidirectional"))
      (node (ref "FMC") (pin "P$35") (pinfunction "P$35_P$35") (pintype "bidirectional"))
    )
    (net (code "29") (name "/CS+") (class "Default")
      (node (ref "FMC") (pin "P$19") (pinfunction "P$19_P$19") (pintype "bidirectional"))
      (node (ref "R15") (pin "2") (pinfunction "2_2") (pintype "passive"))
      (node (ref "U10") (pin "2") (pinfunction "RIN1+_2") (pintype "bidirectional"))
    )
    (net (code "30") (name "/CS-") (class "Default")
      (node (ref "FMC") (pin "P$20") (pinfunction "P$20_P$20") (pintype "bidirectional"))
      (node (ref "R14") (pin "2") (pinfunction "2_2") (pintype "passive"))
      (node (ref "U10") (pin "1") (pinfunction "RIN1-_1") (pintype "bidirectional"))
    )
    (net (code "31") (name "/CS_ISOLATED_SE") (class "Default")
      (node (ref "DO_ISO") (pin "P13") (pinfunction "VOB_P13") (pintype "bidirectional"))
      (node (ref "U4") (pin "2") (pinfunction "DIN1_2") (pintype "bidirectional"))
    )
    (net (code "32") (name "/CS_SE") (class "Default")
      (node (ref "DO_ISO") (pin "P4") (pinfunction "VIB_P4") (pintype "bidirectional"))
      (node (ref "U10") (pin "7") (pinfunction "ROUT1_7") (pintype "bidirectional"))
    )
    (net (code "33") (name "/MISO1+") (class "Default")
      (node (ref "FMC") (pin "P$10") (pinfunction "P$10_P$10") (pintype "bidirectional"))
      (node (ref "R21") (pin "2") (pinfunction "2_2") (pintype "passive"))
      (node (ref "TP2") (pin "TP-2") (pinfunction "TP_TP-2") (pintype "input"))
      (node (ref "U11") (pin "6") (pinfunction "DOUT2+_6") (pintype "bidirectional"))
    )
    (net (code "34") (name "/MISO1+_ISOLATED") (class "Default")
      (node (ref "A_ISOLATED") (pin "B4") (pinfunction "MISO1+_B4") (pintype "bidirectional"))
      (node (ref "R4") (pin "1") (pinfunction "1_1") (pintype "passive"))
      (node (ref "TP1") (pin "TP-4") (pinfunction "TP_TP-4") (pintype "input"))
      (node (ref "U5") (pin "3") (pinfunction "RIN2+_3") (pintype "bidirectional"))
    )
    (net (code "35") (name "/MISO1-") (class "Default")
      (node (ref "FMC") (pin "P$11") (pinfunction "P$11_P$11") (pintype "bidirectional"))
      (node (ref "R20") (pin "2") (pinfunction "2_2") (pintype "passive"))
      (node (ref "U11") (pin "5") (pinfunction "DOUT2-_5") (pintype "bidirectional"))
    )
    (net (code "36") (name "/MISO1_ISOLATED_SE") (class "Default")
      (node (ref "DI_ISO") (pin "P4") (pinfunction "VIB_P4") (pintype "bidirectional"))
      (node (ref "TP1") (pin "TP-5") (pinfunction "TP_TP-5") (pintype "input"))
      (node (ref "U5") (pin "6") (pinfunction "ROUT2_6") (pintype "bidirectional"))
    )
    (net (code "37") (name "/MISO1_SE") (class "Default")
      (node (ref "DI_ISO") (pin "P13") (pinfunction "VOB_P13") (pintype "bidirectional"))
      (node (ref "TP2") (pin "TP-1") (pinfunction "TP_TP-1") (pintype "input"))
      (node (ref "U11") (pin "3") (pinfunction "DIN2_3") (pintype "bidirectional"))
    )
    (net (code "38") (name "/MISO2+") (class "Default")
      (node (ref "FMC") (pin "P$7") (pinfunction "P$7_P$7") (pintype "bidirectional"))
      (node (ref "R23") (pin "2") (pinfunction "2_2") (pintype "passive"))
      (node (ref "U11") (pin "7") (pinfunction "DOUT1+_7") (pintype "bidirectional"))
    )
    (net (code "39") (name "/MISO2-") (class "Default")
      (node (ref "FMC") (pin "P$8") (pinfunction "P$8_P$8") (pintype "bidirectional"))
      (node (ref "R22") (pin "2") (pinfunction "2_2") (pintype "passive"))
      (node (ref "U11") (pin "8") (pinfunction "DOUT1-_8") (pintype "bidirectional"))
    )
    (net (code "40") (name "/MISO2_ISOLATED_SE") (class "Default")
      (node (ref "DI_ISO") (pin "P3") (pinfunction "VIA_P3") (pintype "bidirectional"))
      (node (ref "U5") (pin "7") (pinfunction "ROUT1_7") (pintype "bidirectional"))
    )
    (net (code "41") (name "/MOSI+") (class "Default")
      (node (ref "FMC") (pin "P$13") (pinfunction "P$13_P$13") (pintype "bidirectional"))
      (node (ref "R19") (pin "2") (pinfunction "2_2") (pintype "passive"))
      (node (ref "TP2") (pin "TP-4") (pinfunction "TP_TP-4") (pintype "input"))
      (node (ref "U9") (pin "3") (pinfunction "RIN2+_3") (pintype "bidirectional"))
    )
    (net (code "42") (name "/MOSI+_ISOLATED") (class "Default")
      (node (ref "A_ISOLATED") (pin "B3") (pinfunction "MOSI+_B3") (pintype "bidirectional"))
      (node (ref "TP1") (pin "TP-2") (pinfunction "TP_TP-2") (pintype "input"))
      (node (ref "U3") (pin "6") (pinfunction "DOUT2+_6") (pintype "bidirectional"))
    )
    (net (code "43") (name "/MOSI-") (class "Default")
      (node (ref "FMC") (pin "P$14") (pinfunction "P$14_P$14") (pintype "bidirectional"))
      (node (ref "R18") (pin "2") (pinfunction "2_2") (pintype "passive"))
      (node (ref "U9") (pin "4") (pinfunction "RIN2-_4") (pintype "bidirectional"))
    )
    (net (code "44") (name "/MOSI_ISOLATED_SE") (class "Default")
      (node (ref "DO_ISO") (pin "P11") (pinfunction "VOD_P11") (pintype "bidirectional"))
      (node (ref "TP1") (pin "TP-3") (pinfunction "TP_TP-3") (pintype "input"))
      (node (ref "U3") (pin "3") (pinfunction "DIN2_3") (pintype "bidirectional"))
    )
    (net (code "45") (name "/MOSI_SE") (class "Default")
      (node (ref "DO_ISO") (pin "P6") (pinfunction "VID_P6") (pintype "bidirectional"))
      (node (ref "TP2") (pin "TP-3") (pinfunction "TP_TP-3") (pintype "input"))
      (node (ref "U9") (pin "6") (pinfunction "ROUT2_6") (pintype "bidirectional"))
    )
    (net (code "46") (name "/SCLK+") (class "Default")
      (node (ref "FMC") (pin "P$16") (pinfunction "P$16_P$16") (pintype "bidirectional"))
      (node (ref "R17") (pin "2") (pinfunction "2_2") (pintype "passive"))
      (node (ref "U9") (pin "2") (pinfunction "RIN1+_2") (pintype "bidirectional"))
    )
    (net (code "47") (name "/SCLK-") (class "Default")
      (node (ref "FMC") (pin "P$17") (pinfunction "P$17_P$17") (pintype "bidirectional"))
      (node (ref "R16") (pin "2") (pinfunction "2_2") (pintype "passive"))
      (node (ref "U9") (pin "1") (pinfunction "RIN1-_1") (pintype "bidirectional"))
    )
    (net (code "48") (name "/SCLK_ISOLATED_SE") (class "Default")
      (node (ref "DO_ISO") (pin "P12") (pinfunction "VOC_P12") (pintype "bidirectional"))
      (node (ref "U3") (pin "2") (pinfunction "DIN1_2") (pintype "bidirectional"))
    )
    (net (code "49") (name "/SCLK_SE") (class "Default")
      (node (ref "DO_ISO") (pin "P5") (pinfunction "VIC_P5") (pintype "bidirectional"))
      (node (ref "U9") (pin "7") (pinfunction "ROUT1_7") (pintype "bidirectional"))
    )
    (net (code "50") (name "/TP1_FROM_SMA") (class "Default")
      (node (ref "DI_ISO") (pin "P5") (pinfunction "VIC_P5") (pintype "bidirectional"))
      (node (ref "H21_ISO") (pin "CLK") (pinfunction "1_CLK") (pintype "passive"))
    )
    (net (code "51") (name "/TP1_TO_FPGA") (class "Default")
      (node (ref "DI_ISO") (pin "P12") (pinfunction "VOC_P12") (pintype "bidirectional"))
      (node (ref "FMC") (pin "P$22") (pinfunction "P$22_P$22") (pintype "bidirectional"))
    )
    (net (code "52") (name "/TP2_FROM_SMA") (class "Default")
      (node (ref "DI_ISO") (pin "P6") (pinfunction "VID_P6") (pintype "bidirectional"))
      (node (ref "H22_ISO") (pin "CLK") (pinfunction "1_CLK") (pintype "passive"))
    )
    (net (code "53") (name "/TP2_TO_FPGA") (class "Default")
      (node (ref "DI_ISO") (pin "P11") (pinfunction "VOD_P11") (pintype "bidirectional"))
      (node (ref "FMC") (pin "P$23") (pinfunction "P$23_P$23") (pintype "bidirectional"))
    )
    (net (code "54") (name "/TP3_FROM_FPGA") (class "Default")
      (node (ref "DO_ISO") (pin "P3") (pinfunction "VIA_P3") (pintype "bidirectional"))
      (node (ref "FMC") (pin "P$62") (pinfunction "P$62_P$62") (pintype "bidirectional"))
    )
    (net (code "55") (name "/TP3_TO_SMA") (class "Default")
      (node (ref "DO_ISO") (pin "P14") (pinfunction "VOA_P14") (pintype "bidirectional"))
      (node (ref "G22_ISO") (pin "CLK") (pinfunction "1_CLK") (pintype "passive"))
    )
    (net (code "56") (name "/TP4") (class "Default")
      (node (ref "C10_DIR") (pin "CLK") (pinfunction "1_CLK") (pintype "passive"))
      (node (ref "FMC") (pin "P$130") (pinfunction "P$130_P$130") (pintype "bidirectional"))
    )
    (net (code "57") (name "/TP5") (class "Default")
      (node (ref "C11_DIR") (pin "CLK") (pinfunction "1_CLK") (pintype "passive"))
      (node (ref "FMC") (pin "P$131") (pinfunction "P$131_P$131") (pintype "bidirectional"))
    )
    (net (code "58") (name "/TP6") (class "Default")
      (node (ref "C14_DIR") (pin "CLK") (pinfunction "1_CLK") (pintype "passive"))
      (node (ref "FMC") (pin "P$134") (pinfunction "P$134_P$134") (pintype "bidirectional"))
    )
    (net (code "59") (name "/TP7") (class "Default")
      (node (ref "C15_DIR") (pin "CLK") (pinfunction "1_CLK") (pintype "passive"))
      (node (ref "FMC") (pin "P$135") (pinfunction "P$135_P$135") (pintype "bidirectional"))
    )
    (net (code "60") (name "/TP8") (class "Default")
      (node (ref "C18_DIR") (pin "CLK") (pinfunction "1_CLK") (pintype "passive"))
      (node (ref "FMC") (pin "P$138") (pinfunction "P$138_P$138") (pintype "bidirectional"))
    )
    (net (code "61") (name "/VDD_IN") (class "Default")
      (node (ref "C16") (pin "1") (pinfunction "1_1") (pintype "passive"))
      (node (ref "J2") (pin "1") (pinfunction "PWR_1") (pintype "power_in"))
      (node (ref "LINK-5V") (pin "1") (pinfunction "1_1") (pintype "passive"))
      (node (ref "TP4") (pin "TP-4") (pinfunction "TP_TP-4") (pintype "input"))
      (node (ref "U7") (pin "1") (pinfunction "IN_1") (pintype "power_in"))
      (node (ref "U7") (pin "3") (pinfunction "EN_3") (pintype "input"))
    )
    (net (code "62") (name "GND") (class "Default")
      (node (ref "A") (pin "T6") (pinfunction "GND_T6") (pintype "power_in"))
      (node (ref "B") (pin "T6") (pinfunction "GND_T6") (pintype "power_in"))
      (node (ref "C10_DIR") (pin "GND$1") (pinfunction "2_GND$1") (pintype "passive"))
      (node (ref "C10_DIR") (pin "GND$2") (pinfunction "2_GND$2") (pintype "passive"))
      (node (ref "C10_DIR") (pin "GND$3") (pinfunction "2_GND$3") (pintype "passive"))
      (node (ref "C10_DIR") (pin "GND$4") (pinfunction "2_GND$4") (pintype "passive"))
      (node (ref "C11_DIR") (pin "GND$1") (pinfunction "2_GND$1") (pintype "passive"))
      (node (ref "C11_DIR") (pin "GND$2") (pinfunction "2_GND$2") (pintype "passive"))
      (node (ref "C11_DIR") (pin "GND$3") (pinfunction "2_GND$3") (pintype "passive"))
      (node (ref "C11_DIR") (pin "GND$4") (pinfunction "2_GND$4") (pintype "passive"))
      (node (ref "C14") (pin "1") (pinfunction "1_1") (pintype "passive"))
      (node (ref "C14_DIR") (pin "GND$1") (pinfunction "2_GND$1") (pintype "passive"))
      (node (ref "C14_DIR") (pin "GND$2") (pinfunction "2_GND$2") (pintype "passive"))
      (node (ref "C14_DIR") (pin "GND$3") (pinfunction "2_GND$3") (pintype "passive"))
      (node (ref "C14_DIR") (pin "GND$4") (pinfunction "2_GND$4") (pintype "passive"))
      (node (ref "C15") (pin "1") (pinfunction "1_1") (pintype "passive"))
      (node (ref "C15_DIR") (pin "GND$1") (pinfunction "2_GND$1") (pintype "passive"))
      (node (ref "C15_DIR") (pin "GND$2") (pinfunction "2_GND$2") (pintype "passive"))
      (node (ref "C15_DIR") (pin "GND$3") (pinfunction "2_GND$3") (pintype "passive"))
      (node (ref "C15_DIR") (pin "GND$4") (pinfunction "2_GND$4") (pintype "passive"))
      (node (ref "C16") (pin "2") (pinfunction "2_2") (pintype "passive"))
      (node (ref "C18") (pin "2") (pinfunction "2_2") (pintype "passive"))
      (node (ref "C18_DIR") (pin "GND$1") (pinfunction "2_GND$1") (pintype "passive"))
      (node (ref "C18_DIR") (pin "GND$2") (pinfunction "2_GND$2") (pintype "passive"))
      (node (ref "C18_DIR") (pin "GND$3") (pinfunction "2_GND$3") (pintype "passive"))
      (node (ref "C18_DIR") (pin "GND$4") (pinfunction "2_GND$4") (pintype "passive"))
      (node (ref "C19") (pin "2") (pinfunction "2_2") (pintype "passive"))
      (node (ref "C21") (pin "2") (pinfunction "2_2") (pintype "passive"))
      (node (ref "C22") (pin "2") (pinfunction "2_2") (pintype "passive"))
      (node (ref "C23") (pin "2") (pinfunction "2_2") (pintype "passive"))
      (node (ref "C26") (pin "2") (pinfunction "2_2") (pintype "passive"))
      (node (ref "D3") (pin "C") (pinfunction "C_C") (pintype "passive"))
      (node (ref "DI_ISO") (pin "P15") (pinfunction "GND2_P15") (pintype "bidirectional"))
      (node (ref "DI_ISO") (pin "P9") (pinfunction "GND2_P9") (pintype "bidirectional"))
      (node (ref "DO_ISO") (pin "P2") (pinfunction "GND1_P2") (pintype "bidirectional"))
      (node (ref "DO_ISO") (pin "P8") (pinfunction "GND1_P8") (pintype "bidirectional"))
      (node (ref "FMC") (pin "P$102") (pinfunction "P$102_P$102") (pintype "bidirectional"))
      (node (ref "FMC") (pin "P$105") (pinfunction "P$105_P$105") (pintype "bidirectional"))
      (node (ref "FMC") (pin "P$108") (pinfunction "P$108_P$108") (pintype "bidirectional"))
      (node (ref "FMC") (pin "P$117") (pinfunction "P$117_P$117") (pintype "bidirectional"))
      (node (ref "FMC") (pin "P$119") (pinfunction "P$119_P$119") (pintype "bidirectional"))
      (node (ref "FMC") (pin "P$12") (pinfunction "P$12_P$12") (pintype "bidirectional"))
      (node (ref "FMC") (pin "P$121") (pinfunction "P$121_P$121") (pintype "bidirectional"))
      (node (ref "FMC") (pin "P$124") (pinfunction "P$124_P$124") (pintype "bidirectional"))
      (node (ref "FMC") (pin "P$125") (pinfunction "P$125_P$125") (pintype "bidirectional"))
      (node (ref "FMC") (pin "P$128") (pinfunction "P$128_P$128") (pintype "bidirectional"))
      (node (ref "FMC") (pin "P$129") (pinfunction "P$129_P$129") (pintype "bidirectional"))
      (node (ref "FMC") (pin "P$132") (pinfunction "P$132_P$132") (pintype "bidirectional"))
      (node (ref "FMC") (pin "P$133") (pinfunction "P$133_P$133") (pintype "bidirectional"))
      (node (ref "FMC") (pin "P$136") (pinfunction "P$136_P$136") (pintype "bidirectional"))
      (node (ref "FMC") (pin "P$137") (pinfunction "P$137_P$137") (pintype "bidirectional"))
      (node (ref "FMC") (pin "P$140") (pinfunction "P$140_P$140") (pintype "bidirectional"))
      (node (ref "FMC") (pin "P$141") (pinfunction "P$141_P$141") (pintype "bidirectional"))
      (node (ref "FMC") (pin "P$144") (pinfunction "P$144_P$144") (pintype "bidirectional"))
      (node (ref "FMC") (pin "P$145") (pinfunction "P$145_P$145") (pintype "bidirectional"))
      (node (ref "FMC") (pin "P$148") (pinfunction "P$148_P$148") (pintype "bidirectional"))
      (node (ref "FMC") (pin "P$149") (pinfunction "P$149_P$149") (pintype "bidirectional"))
      (node (ref "FMC") (pin "P$15") (pinfunction "P$15_P$15") (pintype "bidirectional"))
      (node (ref "FMC") (pin "P$152") (pinfunction "P$152_P$152") (pintype "bidirectional"))
      (node (ref "FMC") (pin "P$153") (pinfunction "P$153_P$153") (pintype "bidirectional"))
      (node (ref "FMC") (pin "P$156") (pinfunction "P$156_P$156") (pintype "bidirectional"))
      (node (ref "FMC") (pin "P$158") (pinfunction "P$158_P$158") (pintype "bidirectional"))
      (node (ref "FMC") (pin "P$160") (pinfunction "P$160_P$160") (pintype "bidirectional"))
      (node (ref "FMC") (pin "P$18") (pinfunction "P$18_P$18") (pintype "bidirectional"))
      (node (ref "FMC") (pin "P$21") (pinfunction "P$21_P$21") (pintype "bidirectional"))
      (node (ref "FMC") (pin "P$24") (pinfunction "P$24_P$24") (pintype "bidirectional"))
      (node (ref "FMC") (pin "P$27") (pinfunction "P$27_P$27") (pintype "bidirectional"))
      (node (ref "FMC") (pin "P$3") (pinfunction "P$3_P$3") (pintype "bidirectional"))
      (node (ref "FMC") (pin "P$30") (pinfunction "P$30_P$30") (pintype "bidirectional"))
      (node (ref "FMC") (pin "P$33") (pinfunction "P$33_P$33") (pintype "bidirectional"))
      (node (ref "FMC") (pin "P$36") (pinfunction "P$36_P$36") (pintype "bidirectional"))
      (node (ref "FMC") (pin "P$39") (pinfunction "P$39_P$39") (pintype "bidirectional"))
      (node (ref "FMC") (pin "P$41") (pinfunction "P$41_P$41") (pintype "bidirectional"))
      (node (ref "FMC") (pin "P$44") (pinfunction "P$44_P$44") (pintype "bidirectional"))
      (node (ref "FMC") (pin "P$45") (pinfunction "P$45_P$45") (pintype "bidirectional"))
      (node (ref "FMC") (pin "P$48") (pinfunction "P$48_P$48") (pintype "bidirectional"))
      (node (ref "FMC") (pin "P$51") (pinfunction "P$51_P$51") (pintype "bidirectional"))
      (node (ref "FMC") (pin "P$54") (pinfunction "P$54_P$54") (pintype "bidirectional"))
      (node (ref "FMC") (pin "P$57") (pinfunction "P$57_P$57") (pintype "bidirectional"))
      (node (ref "FMC") (pin "P$6") (pinfunction "P$6_P$6") (pintype "bidirectional"))
      (node (ref "FMC") (pin "P$60") (pinfunction "P$60_P$60") (pintype "bidirectional"))
      (node (ref "FMC") (pin "P$63") (pinfunction "P$63_P$63") (pintype "bidirectional"))
      (node (ref "FMC") (pin "P$66") (pinfunction "P$66_P$66") (pintype "bidirectional"))
      (node (ref "FMC") (pin "P$69") (pinfunction "P$69_P$69") (pintype "bidirectional"))
      (node (ref "FMC") (pin "P$72") (pinfunction "P$72_P$72") (pintype "bidirectional"))
      (node (ref "FMC") (pin "P$75") (pinfunction "P$75_P$75") (pintype "bidirectional"))
      (node (ref "FMC") (pin "P$78") (pinfunction "P$78_P$78") (pintype "bidirectional"))
      (node (ref "FMC") (pin "P$80") (pinfunction "P$80_P$80") (pintype "bidirectional"))
      (node (ref "FMC") (pin "P$82") (pinfunction "P$82_P$82") (pintype "bidirectional"))
      (node (ref "FMC") (pin "P$83") (pinfunction "P$83_P$83") (pintype "bidirectional"))
      (node (ref "FMC") (pin "P$86") (pinfunction "P$86_P$86") (pintype "bidirectional"))
      (node (ref "FMC") (pin "P$87") (pinfunction "P$87_P$87") (pintype "bidirectional"))
      (node (ref "FMC") (pin "P$9") (pinfunction "P$9_P$9") (pintype "bidirectional"))
      (node (ref "FMC") (pin "P$90") (pinfunction "P$90_P$90") (pintype "bidirectional"))
      (node (ref "FMC") (pin "P$93") (pinfunction "P$93_P$93") (pintype "bidirectional"))
      (node (ref "FMC") (pin "P$96") (pinfunction "P$96_P$96") (pintype "bidirectional"))
      (node (ref "FMC") (pin "P$99") (pinfunction "P$99_P$99") (pintype "bidirectional"))
      (node (ref "J2") (pin "2") (pinfunction "GND1_2") (pintype "power_in"))
      (node (ref "J2") (pin "3") (pinfunction "GND2_3") (pintype "power_in"))
      (node (ref "LINK_GNDS") (pin "3") (pinfunction "3_3") (pintype "passive"))
      (node (ref "R10") (pin "1") (pinfunction "1_1") (pintype "passive"))
      (node (ref "R11") (pin "1") (pinfunction "1_1") (pintype "passive"))
      (node (ref "R9") (pin "2") (pinfunction "2_2") (pintype "passive"))
      (node (ref "TP2") (pin "TP-5") (pinfunction "TP_TP-5") (pintype "input"))
      (node (ref "TP4") (pin "TP-5") (pinfunction "TP_TP-5") (pintype "input"))
      (node (ref "U10") (pin "5") (pinfunction "GND_5") (pintype "bidirectional"))
      (node (ref "U11") (pin "4") (pinfunction "GND_4") (pintype "bidirectional"))
      (node (ref "U6") (pin "P1") (pinfunction "GND_P1") (pintype "bidirectional"))
      (node (ref "U7") (pin "2") (pinfunction "GND_2") (pintype "power_in"))
      (node (ref "U9") (pin "5") (pinfunction "GND_5") (pintype "bidirectional"))
    )
    (net (code "63") (name "GND_ISO") (class "Default")
      (node (ref "A_ISOLATED") (pin "T6") (pinfunction "GND_T6") (pintype "power_in"))
      (node (ref "C1") (pin "2") (pinfunction "2_2") (pintype "passive"))
      (node (ref "C10") (pin "2") (pinfunction "2_2") (pintype "passive"))
      (node (ref "C11") (pin "2") (pinfunction "2_2") (pintype "passive"))
      (node (ref "C12") (pin "1") (pinfunction "1_1") (pintype "passive"))
      (node (ref "C13") (pin "1") (pinfunction "1_1") (pintype "passive"))
      (node (ref "C3") (pin "2") (pinfunction "2_2") (pintype "passive"))
      (node (ref "C4") (pin "2") (pinfunction "2_2") (pintype "passive"))
      (node (ref "C5") (pin "2") (pinfunction "2_2") (pintype "passive"))
      (node (ref "C6") (pin "2") (pinfunction "2_2") (pintype "passive"))
      (node (ref "C7") (pin "2") (pinfunction "2_2") (pintype "passive"))
      (node (ref "C8") (pin "2") (pinfunction "2_2") (pintype "passive"))
      (node (ref "C9") (pin "2") (pinfunction "2_2") (pintype "passive"))
      (node (ref "D1") (pin "C") (pinfunction "C_C") (pintype "passive"))
      (node (ref "D2") (pin "C") (pinfunction "C_C") (pintype "passive"))
      (node (ref "DI_ISO") (pin "P2") (pinfunction "GND1_P2") (pintype "bidirectional"))
      (node (ref "DI_ISO") (pin "P8") (pinfunction "GND1_P8") (pintype "bidirectional"))
      (node (ref "DO_ISO") (pin "P15") (pinfunction "GND2_P15") (pintype "bidirectional"))
      (node (ref "DO_ISO") (pin "P9") (pinfunction "GND2_P9") (pintype "bidirectional"))
      (node (ref "G22_ISO") (pin "GND$1") (pinfunction "2_GND$1") (pintype "passive"))
      (node (ref "G22_ISO") (pin "GND$2") (pinfunction "2_GND$2") (pintype "passive"))
      (node (ref "G22_ISO") (pin "GND$3") (pinfunction "2_GND$3") (pintype "passive"))
      (node (ref "G22_ISO") (pin "GND$4") (pinfunction "2_GND$4") (pintype "passive"))
      (node (ref "H21_ISO") (pin "GND$1") (pinfunction "2_GND$1") (pintype "passive"))
      (node (ref "H21_ISO") (pin "GND$2") (pinfunction "2_GND$2") (pintype "passive"))
      (node (ref "H21_ISO") (pin "GND$3") (pinfunction "2_GND$3") (pintype "passive"))
      (node (ref "H21_ISO") (pin "GND$4") (pinfunction "2_GND$4") (pintype "passive"))
      (node (ref "H22_ISO") (pin "GND$1") (pinfunction "2_GND$1") (pintype "passive"))
      (node (ref "H22_ISO") (pin "GND$2") (pinfunction "2_GND$2") (pintype "passive"))
      (node (ref "H22_ISO") (pin "GND$3") (pinfunction "2_GND$3") (pintype "passive"))
      (node (ref "H22_ISO") (pin "GND$4") (pinfunction "2_GND$4") (pintype "passive"))
      (node (ref "J1") (pin "2") (pinfunction "GND1_2") (pintype "power_in"))
      (node (ref "J1") (pin "3") (pinfunction "GND2_3") (pintype "power_in"))
      (node (ref "LINK_GNDS") (pin "2") (pinfunction "2_2") (pintype "passive"))
      (node (ref "R6") (pin "2") (pinfunction "2_2") (pintype "passive"))
      (node (ref "R7") (pin "1") (pinfunction "1_1") (pintype "passive"))
      (node (ref "TP1") (pin "TP-1") (pinfunction "TP_TP-1") (pintype "input"))
      (node (ref "TP3") (pin "TP-1") (pinfunction "TP_TP-1") (pintype "input"))
      (node (ref "TP3") (pin "TP-5") (pinfunction "TP_TP-5") (pintype "input"))
      (node (ref "U1") (pin "2") (pinfunction "GND_2") (pintype "power_in"))
      (node (ref "U2") (pin "2") (pinfunction "GND_2") (pintype "power_in"))
      (node (ref "U3") (pin "4") (pinfunction "GND_4") (pintype "bidirectional"))
      (node (ref "U4") (pin "4") (pinfunction "GND_4") (pintype "bidirectional"))
      (node (ref "U5") (pin "5") (pinfunction "GND_5") (pintype "bidirectional"))
      (node (ref "U6") (pin "P3") (pinfunction "0V_P3") (pintype "bidirectional"))
    )
    (net (code "64") (name "Net-(A_ISOLATED-MISO1-)") (class "Default")
      (node (ref "A_ISOLATED") (pin "T4") (pinfunction "MISO1-_T4") (pintype "bidirectional"))
      (node (ref "R4") (pin "2") (pinfunction "2_2") (pintype "passive"))
      (node (ref "U5") (pin "4") (pinfunction "RIN2-_4") (pintype "bidirectional"))
    )
    (net (code "65") (name "Net-(A_ISOLATED-MISO2+)") (class "Default")
      (node (ref "A_ISOLATED") (pin "B5") (pinfunction "MISO2+_B5") (pintype "bidirectional"))
      (node (ref "R3") (pin "1") (pinfunction "1_1") (pintype "passive"))
      (node (ref "U5") (pin "2") (pinfunction "RIN1+_2") (pintype "bidirectional"))
    )
    (net (code "66") (name "Net-(A_ISOLATED-MISO2-)") (class "Default")
      (node (ref "A_ISOLATED") (pin "T5") (pinfunction "MISO2-_T5") (pintype "bidirectional"))
      (node (ref "R3") (pin "2") (pinfunction "2_2") (pintype "passive"))
      (node (ref "U5") (pin "1") (pinfunction "RIN1-_1") (pintype "bidirectional"))
    )
    (net (code "67") (name "Net-(A_ISOLATED-MOSI-)") (class "Default")
      (node (ref "A_ISOLATED") (pin "T3") (pinfunction "MOSI-_T3") (pintype "bidirectional"))
      (node (ref "U3") (pin "5") (pinfunction "DOUT2-_5") (pintype "bidirectional"))
    )
    (net (code "68") (name "Net-(A_ISOLATED-SCLK+)") (class "Default")
      (node (ref "A_ISOLATED") (pin "B2") (pinfunction "SCLK+_B2") (pintype "bidirectional"))
      (node (ref "U3") (pin "7") (pinfunction "DOUT1+_7") (pintype "bidirectional"))
    )
    (net (code "69") (name "Net-(A_ISOLATED-SCLK-)") (class "Default")
      (node (ref "A_ISOLATED") (pin "T2") (pinfunction "SCLK-_T2") (pintype "bidirectional"))
      (node (ref "U3") (pin "8") (pinfunction "DOUT1-_8") (pintype "bidirectional"))
    )
    (net (code "70") (name "Net-(A_ISOLATED-~{CS}+)") (class "Default")
      (node (ref "A_ISOLATED") (pin "B1") (pinfunction "~{CS}+_B1") (pintype "bidirectional"))
      (node (ref "U4") (pin "7") (pinfunction "DOUT1+_7") (pintype "bidirectional"))
    )
    (net (code "71") (name "Net-(A_ISOLATED-~{CS}-)") (class "Default")
      (node (ref "A_ISOLATED") (pin "T1") (pinfunction "~{CS}-_T1") (pintype "bidirectional"))
      (node (ref "U4") (pin "8") (pinfunction "DOUT1-_8") (pintype "bidirectional"))
    )
    (net (code "72") (name "Net-(D1-PadA)") (class "Default")
      (node (ref "D1") (pin "A") (pinfunction "A_A") (pintype "passive"))
      (node (ref "R1") (pin "2") (pinfunction "2_2") (pintype "passive"))
    )
    (net (code "73") (name "Net-(D2-PadA)") (class "Default")
      (node (ref "D2") (pin "A") (pinfunction "A_A") (pintype "passive"))
      (node (ref "R2") (pin "2") (pinfunction "2_2") (pintype "passive"))
    )
    (net (code "74") (name "Net-(D3-PadA)") (class "Default")
      (node (ref "D3") (pin "A") (pinfunction "A_A") (pintype "passive"))
      (node (ref "R12") (pin "2") (pinfunction "2_2") (pintype "passive"))
    )
    (net (code "75") (name "Net-(DI_ISO-VOA)") (class "Default")
      (node (ref "DI_ISO") (pin "P14") (pinfunction "VOA_P14") (pintype "bidirectional"))
      (node (ref "U11") (pin "2") (pinfunction "DIN1_2") (pintype "bidirectional"))
    )
    (net (code "76") (name "Net-(U1-FB)") (class "Default")
      (node (ref "C2") (pin "2") (pinfunction "2_2") (pintype "passive"))
      (node (ref "R5") (pin "1") (pinfunction "1_1") (pintype "passive"))
      (node (ref "R6") (pin "1") (pinfunction "1_1") (pintype "passive"))
      (node (ref "U1") (pin "5") (pinfunction "FB_5") (pintype "input"))
    )
    (net (code "77") (name "Net-(U1-NR)") (class "Default")
      (node (ref "C4") (pin "1") (pinfunction "1_1") (pintype "passive"))
      (node (ref "U1") (pin "4") (pinfunction "NR_4") (pintype "passive"))
    )
    (net (code "78") (name "Net-(U2-NR)") (class "Default")
      (node (ref "C5") (pin "1") (pinfunction "1_1") (pintype "passive"))
      (node (ref "U2") (pin "4") (pinfunction "NR_4") (pintype "passive"))
    )
    (net (code "79") (name "Net-(U4-DIN2)") (class "Default")
      (node (ref "R7") (pin "2") (pinfunction "2_2") (pintype "passive"))
      (node (ref "U4") (pin "3") (pinfunction "DIN2_3") (pintype "bidirectional"))
    )
    (net (code "80") (name "Net-(U7-FB)") (class "Default")
      (node (ref "C25") (pin "2") (pinfunction "2_2") (pintype "passive"))
      (node (ref "R8") (pin "1") (pinfunction "1_1") (pintype "passive"))
      (node (ref "R9") (pin "1") (pinfunction "1_1") (pintype "passive"))
      (node (ref "U7") (pin "5") (pinfunction "FB_5") (pintype "input"))
    )
    (net (code "81") (name "Net-(U7-NR)") (class "Default")
      (node (ref "C19") (pin "1") (pinfunction "1_1") (pintype "passive"))
      (node (ref "U7") (pin "4") (pinfunction "NR_4") (pintype "passive"))
    )
    (net (code "82") (name "Net-(U10-RIN2+)") (class "Default")
      (node (ref "R11") (pin "2") (pinfunction "2_2") (pintype "passive"))
      (node (ref "U10") (pin "3") (pinfunction "RIN2+_3") (pintype "bidirectional"))
    )
    (net (code "83") (name "Net-(U10-RIN2-)") (class "Default")
      (node (ref "R10") (pin "2") (pinfunction "2_2") (pintype "passive"))
      (node (ref "U10") (pin "4") (pinfunction "RIN2-_4") (pintype "bidirectional"))
    )
    (net (code "84") (name "unconnected-(FMC-PadP$1)") (class "Default")
      (node (ref "FMC") (pin "P$1") (pinfunction "P$1_P$1") (pintype "bidirectional"))
    )
    (net (code "85") (name "unconnected-(FMC-PadP$2)") (class "Default")
      (node (ref "FMC") (pin "P$2") (pinfunction "P$2_P$2") (pintype "bidirectional"))
    )
    (net (code "86") (name "unconnected-(FMC-PadP$4)") (class "Default")
      (node (ref "FMC") (pin "P$4") (pinfunction "P$4_P$4") (pintype "bidirectional"))
    )
    (net (code "87") (name "unconnected-(FMC-PadP$5)") (class "Default")
      (node (ref "FMC") (pin "P$5") (pinfunction "P$5_P$5") (pintype "bidirectional"))
    )
    (net (code "88") (name "unconnected-(FMC-PadP$40)") (class "Default")
      (node (ref "FMC") (pin "P$40") (pinfunction "P$40_P$40") (pintype "bidirectional"))
    )
    (net (code "89") (name "unconnected-(FMC-PadP$42)") (class "Default")
      (node (ref "FMC") (pin "P$42") (pinfunction "P$42_P$42") (pintype "bidirectional"))
    )
    (net (code "90") (name "unconnected-(FMC-PadP$43)") (class "Default")
      (node (ref "FMC") (pin "P$43") (pinfunction "P$43_P$43") (pintype "bidirectional"))
    )
    (net (code "91") (name "unconnected-(FMC-PadP$46)") (class "Default")
      (node (ref "FMC") (pin "P$46") (pinfunction "P$46_P$46") (pintype "bidirectional"))
    )
    (net (code "92") (name "unconnected-(FMC-PadP$47)") (class "Default")
      (node (ref "FMC") (pin "P$47") (pinfunction "P$47_P$47") (pintype "bidirectional"))
    )
    (net (code "93") (name "unconnected-(FMC-PadP$49)") (class "Default")
      (node (ref "FMC") (pin "P$49") (pinfunction "P$49_P$49") (pintype "bidirectional"))
    )
    (net (code "94") (name "unconnected-(FMC-PadP$50)") (class "Default")
      (node (ref "FMC") (pin "P$50") (pinfunction "P$50_P$50") (pintype "bidirectional"))
    )
    (net (code "95") (name "unconnected-(FMC-PadP$52)") (class "Default")
      (node (ref "FMC") (pin "P$52") (pinfunction "P$52_P$52") (pintype "bidirectional"))
    )
    (net (code "96") (name "unconnected-(FMC-PadP$53)") (class "Default")
      (node (ref "FMC") (pin "P$53") (pinfunction "P$53_P$53") (pintype "bidirectional"))
    )
    (net (code "97") (name "unconnected-(FMC-PadP$55)") (class "Default")
      (node (ref "FMC") (pin "P$55") (pinfunction "P$55_P$55") (pintype "bidirectional"))
    )
    (net (code "98") (name "unconnected-(FMC-PadP$56)") (class "Default")
      (node (ref "FMC") (pin "P$56") (pinfunction "P$56_P$56") (pintype "bidirectional"))
    )
    (net (code "99") (name "unconnected-(FMC-PadP$58)") (class "Default")
      (node (ref "FMC") (pin "P$58") (pinfunction "P$58_P$58") (pintype "bidirectional"))
    )
    (net (code "100") (name "unconnected-(FMC-PadP$59)") (class "Default")
      (node (ref "FMC") (pin "P$59") (pinfunction "P$59_P$59") (pintype "bidirectional"))
    )
    (net (code "101") (name "unconnected-(FMC-PadP$61)") (class "Default")
      (node (ref "FMC") (pin "P$61") (pinfunction "P$61_P$61") (pintype "bidirectional"))
    )
    (net (code "102") (name "unconnected-(FMC-PadP$64)") (class "Default")
      (node (ref "FMC") (pin "P$64") (pinfunction "P$64_P$64") (pintype "bidirectional"))
    )
    (net (code "103") (name "unconnected-(FMC-PadP$65)") (class "Default")
      (node (ref "FMC") (pin "P$65") (pinfunction "P$65_P$65") (pintype "bidirectional"))
    )
    (net (code "104") (name "unconnected-(FMC-PadP$67)") (class "Default")
      (node (ref "FMC") (pin "P$67") (pinfunction "P$67_P$67") (pintype "bidirectional"))
    )
    (net (code "105") (name "unconnected-(FMC-PadP$68)") (class "Default")
      (node (ref "FMC") (pin "P$68") (pinfunction "P$68_P$68") (pintype "bidirectional"))
    )
    (net (code "106") (name "unconnected-(FMC-PadP$70)") (class "Default")
      (node (ref "FMC") (pin "P$70") (pinfunction "P$70_P$70") (pintype "bidirectional"))
    )
    (net (code "107") (name "unconnected-(FMC-PadP$71)") (class "Default")
      (node (ref "FMC") (pin "P$71") (pinfunction "P$71_P$71") (pintype "bidirectional"))
    )
    (net (code "108") (name "unconnected-(FMC-PadP$73)") (class "Default")
      (node (ref "FMC") (pin "P$73") (pinfunction "P$73_P$73") (pintype "bidirectional"))
    )
    (net (code "109") (name "unconnected-(FMC-PadP$74)") (class "Default")
      (node (ref "FMC") (pin "P$74") (pinfunction "P$74_P$74") (pintype "bidirectional"))
    )
    (net (code "110") (name "unconnected-(FMC-PadP$76)") (class "Default")
      (node (ref "FMC") (pin "P$76") (pinfunction "P$76_P$76") (pintype "bidirectional"))
    )
    (net (code "111") (name "unconnected-(FMC-PadP$77)") (class "Default")
      (node (ref "FMC") (pin "P$77") (pinfunction "P$77_P$77") (pintype "bidirectional"))
    )
    (net (code "112") (name "unconnected-(FMC-PadP$79)") (class "Default")
      (node (ref "FMC") (pin "P$79") (pinfunction "P$79_P$79") (pintype "bidirectional"))
    )
    (net (code "113") (name "unconnected-(FMC-PadP$81)") (class "Default")
      (node (ref "FMC") (pin "P$81") (pinfunction "P$81_P$81") (pintype "bidirectional"))
    )
    (net (code "114") (name "unconnected-(FMC-PadP$84)") (class "Default")
      (node (ref "FMC") (pin "P$84") (pinfunction "P$84_P$84") (pintype "bidirectional"))
    )
    (net (code "115") (name "unconnected-(FMC-PadP$85)") (class "Default")
      (node (ref "FMC") (pin "P$85") (pinfunction "P$85_P$85") (pintype "bidirectional"))
    )
    (net (code "116") (name "unconnected-(FMC-PadP$88)") (class "Default")
      (node (ref "FMC") (pin "P$88") (pinfunction "P$88_P$88") (pintype "bidirectional"))
    )
    (net (code "117") (name "unconnected-(FMC-PadP$89)") (class "Default")
      (node (ref "FMC") (pin "P$89") (pinfunction "P$89_P$89") (pintype "bidirectional"))
    )
    (net (code "118") (name "unconnected-(FMC-PadP$91)") (class "Default")
      (node (ref "FMC") (pin "P$91") (pinfunction "P$91_P$91") (pintype "bidirectional"))
    )
    (net (code "119") (name "unconnected-(FMC-PadP$92)") (class "Default")
      (node (ref "FMC") (pin "P$92") (pinfunction "P$92_P$92") (pintype "bidirectional"))
    )
    (net (code "120") (name "unconnected-(FMC-PadP$94)") (class "Default")
      (node (ref "FMC") (pin "P$94") (pinfunction "P$94_P$94") (pintype "bidirectional"))
    )
    (net (code "121") (name "unconnected-(FMC-PadP$95)") (class "Default")
      (node (ref "FMC") (pin "P$95") (pinfunction "P$95_P$95") (pintype "bidirectional"))
    )
    (net (code "122") (name "unconnected-(FMC-PadP$97)") (class "Default")
      (node (ref "FMC") (pin "P$97") (pinfunction "P$97_P$97") (pintype "bidirectional"))
    )
    (net (code "123") (name "unconnected-(FMC-PadP$98)") (class "Default")
      (node (ref "FMC") (pin "P$98") (pinfunction "P$98_P$98") (pintype "bidirectional"))
    )
    (net (code "124") (name "unconnected-(FMC-PadP$100)") (class "Default")
      (node (ref "FMC") (pin "P$100") (pinfunction "P$100_P$100") (pintype "bidirectional"))
    )
    (net (code "125") (name "unconnected-(FMC-PadP$101)") (class "Default")
      (node (ref "FMC") (pin "P$101") (pinfunction "P$101_P$101") (pintype "bidirectional"))
    )
    (net (code "126") (name "unconnected-(FMC-PadP$103)") (class "Default")
      (node (ref "FMC") (pin "P$103") (pinfunction "P$103_P$103") (pintype "bidirectional"))
    )
    (net (code "127") (name "unconnected-(FMC-PadP$104)") (class "Default")
      (node (ref "FMC") (pin "P$104") (pinfunction "P$104_P$104") (pintype "bidirectional"))
    )
    (net (code "128") (name "unconnected-(FMC-PadP$106)") (class "Default")
      (node (ref "FMC") (pin "P$106") (pinfunction "P$106_P$106") (pintype "bidirectional"))
    )
    (net (code "129") (name "unconnected-(FMC-PadP$107)") (class "Default")
      (node (ref "FMC") (pin "P$107") (pinfunction "P$107_P$107") (pintype "bidirectional"))
    )
    (net (code "130") (name "unconnected-(FMC-PadP$109)") (class "Default")
      (node (ref "FMC") (pin "P$109") (pinfunction "P$109_P$109") (pintype "bidirectional"))
    )
    (net (code "131") (name "unconnected-(FMC-PadP$110)") (class "Default")
      (node (ref "FMC") (pin "P$110") (pinfunction "P$110_P$110") (pintype "bidirectional"))
    )
    (net (code "132") (name "unconnected-(FMC-PadP$111)") (class "Default")
      (node (ref "FMC") (pin "P$111") (pinfunction "P$111_P$111") (pintype "bidirectional"))
    )
    (net (code "133") (name "unconnected-(FMC-PadP$112)") (class "Default")
      (node (ref "FMC") (pin "P$112") (pinfunction "P$112_P$112") (pintype "bidirectional"))
    )
    (net (code "134") (name "unconnected-(FMC-PadP$113)") (class "Default")
      (node (ref "FMC") (pin "P$113") (pinfunction "P$113_P$113") (pintype "bidirectional"))
    )
    (net (code "135") (name "unconnected-(FMC-PadP$114)") (class "Default")
      (node (ref "FMC") (pin "P$114") (pinfunction "P$114_P$114") (pintype "bidirectional"))
    )
    (net (code "136") (name "unconnected-(FMC-PadP$115)") (class "Default")
      (node (ref "FMC") (pin "P$115") (pinfunction "P$115_P$115") (pintype "bidirectional"))
    )
    (net (code "137") (name "unconnected-(FMC-PadP$122)") (class "Default")
      (node (ref "FMC") (pin "P$122") (pinfunction "P$122_P$122") (pintype "bidirectional"))
    )
    (net (code "138") (name "unconnected-(FMC-PadP$123)") (class "Default")
      (node (ref "FMC") (pin "P$123") (pinfunction "P$123_P$123") (pintype "bidirectional"))
    )
    (net (code "139") (name "unconnected-(FMC-PadP$126)") (class "Default")
      (node (ref "FMC") (pin "P$126") (pinfunction "P$126_P$126") (pintype "bidirectional"))
    )
    (net (code "140") (name "unconnected-(FMC-PadP$127)") (class "Default")
      (node (ref "FMC") (pin "P$127") (pinfunction "P$127_P$127") (pintype "bidirectional"))
    )
    (net (code "141") (name "unconnected-(FMC-PadP$139)") (class "Default")
      (node (ref "FMC") (pin "P$139") (pinfunction "P$139_P$139") (pintype "bidirectional"))
    )
    (net (code "142") (name "unconnected-(FMC-PadP$142)") (class "Default")
      (node (ref "FMC") (pin "P$142") (pinfunction "P$142_P$142") (pintype "bidirectional"))
    )
    (net (code "143") (name "unconnected-(FMC-PadP$143)") (class "Default")
      (node (ref "FMC") (pin "P$143") (pinfunction "P$143_P$143") (pintype "bidirectional"))
    )
    (net (code "144") (name "unconnected-(FMC-PadP$146)") (class "Default")
      (node (ref "FMC") (pin "P$146") (pinfunction "P$146_P$146") (pintype "bidirectional"))
    )
    (net (code "145") (name "unconnected-(FMC-PadP$147)") (class "Default")
      (node (ref "FMC") (pin "P$147") (pinfunction "P$147_P$147") (pintype "bidirectional"))
    )
    (net (code "146") (name "unconnected-(FMC-PadP$150)") (class "Default")
      (node (ref "FMC") (pin "P$150") (pinfunction "P$150_P$150") (pintype "bidirectional"))
    )
    (net (code "147") (name "unconnected-(FMC-PadP$151)") (class "Default")
      (node (ref "FMC") (pin "P$151") (pinfunction "P$151_P$151") (pintype "bidirectional"))
    )
    (net (code "148") (name "unconnected-(FMC-PadP$154)") (class "Default")
      (node (ref "FMC") (pin "P$154") (pinfunction "P$154_P$154") (pintype "bidirectional"))
    )
    (net (code "149") (name "unconnected-(LINK_GNDS-Pad1)") (class "Default")
      (node (ref "LINK_GNDS") (pin "1") (pinfunction "1_1") (pintype "passive"))
    )
    (net (code "150") (name "unconnected-(U4-DOUT2+-Pad6)") (class "Default")
      (node (ref "U4") (pin "6") (pinfunction "DOUT2+_6") (pintype "bidirectional"))
    )
    (net (code "151") (name "unconnected-(U4-DOUT2--Pad5)") (class "Default")
      (node (ref "U4") (pin "5") (pinfunction "DOUT2-_5") (pintype "bidirectional"))
    )
    (net (code "152") (name "unconnected-(U10-ROUT2-Pad6)") (class "Default")
      (node (ref "U10") (pin "6") (pinfunction "ROUT2_6") (pintype "bidirectional"))
    )
  )
)
